# PS-001.net
KiCad netlist of a schematic drawn in EAGLE
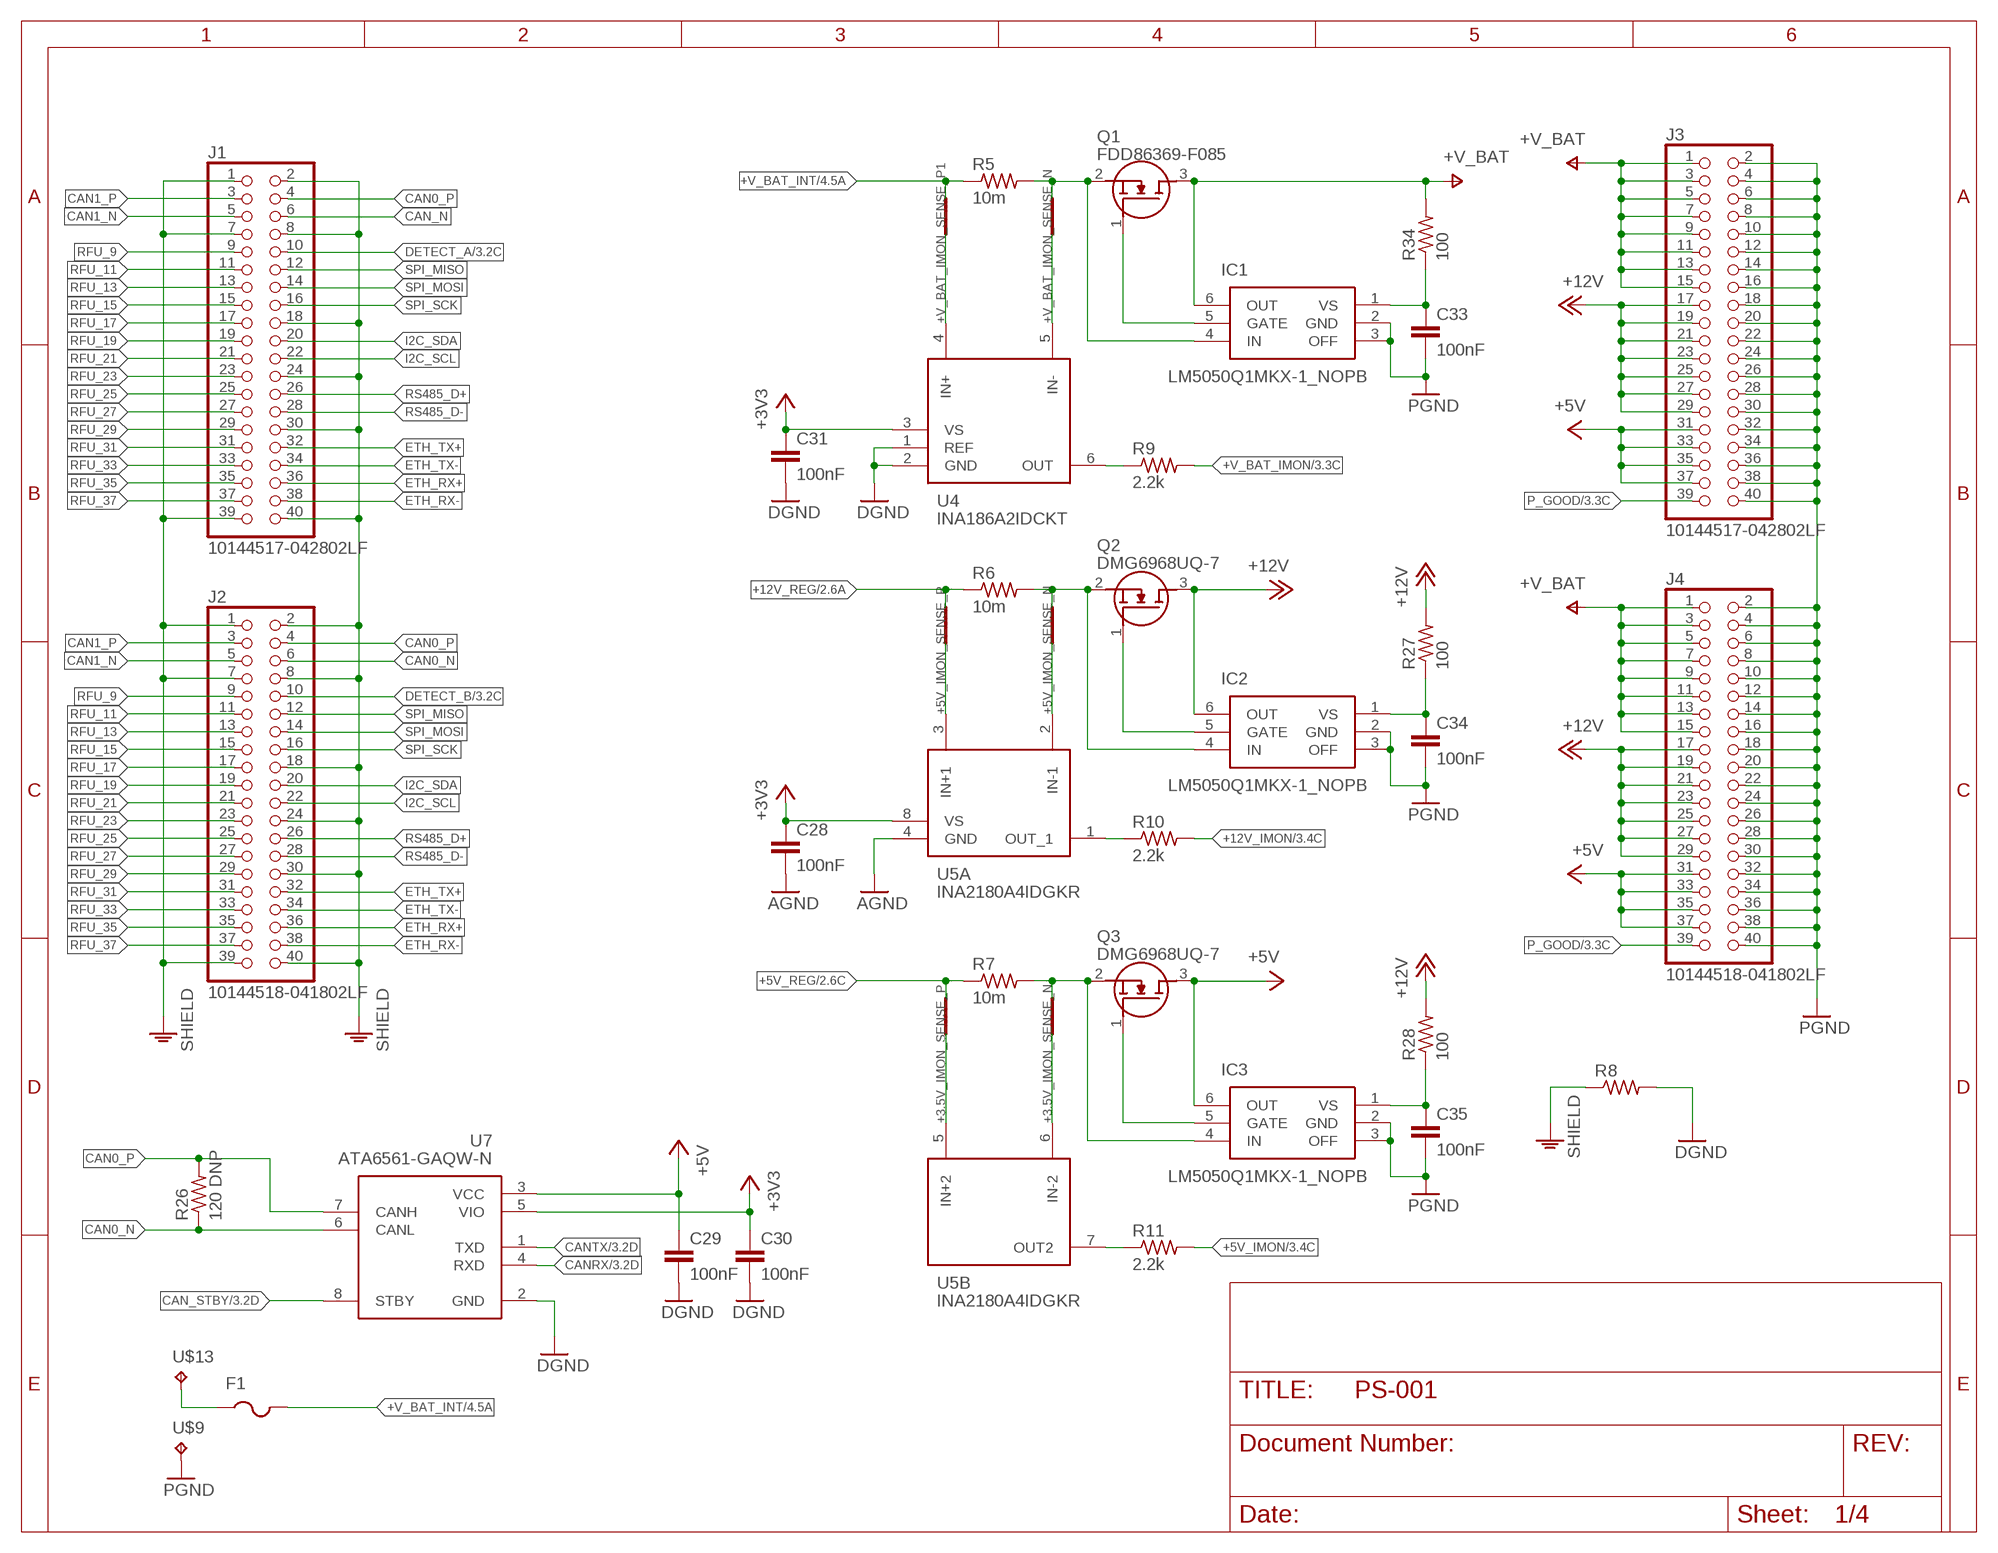
[diagram p0: schematic, sheet 1]
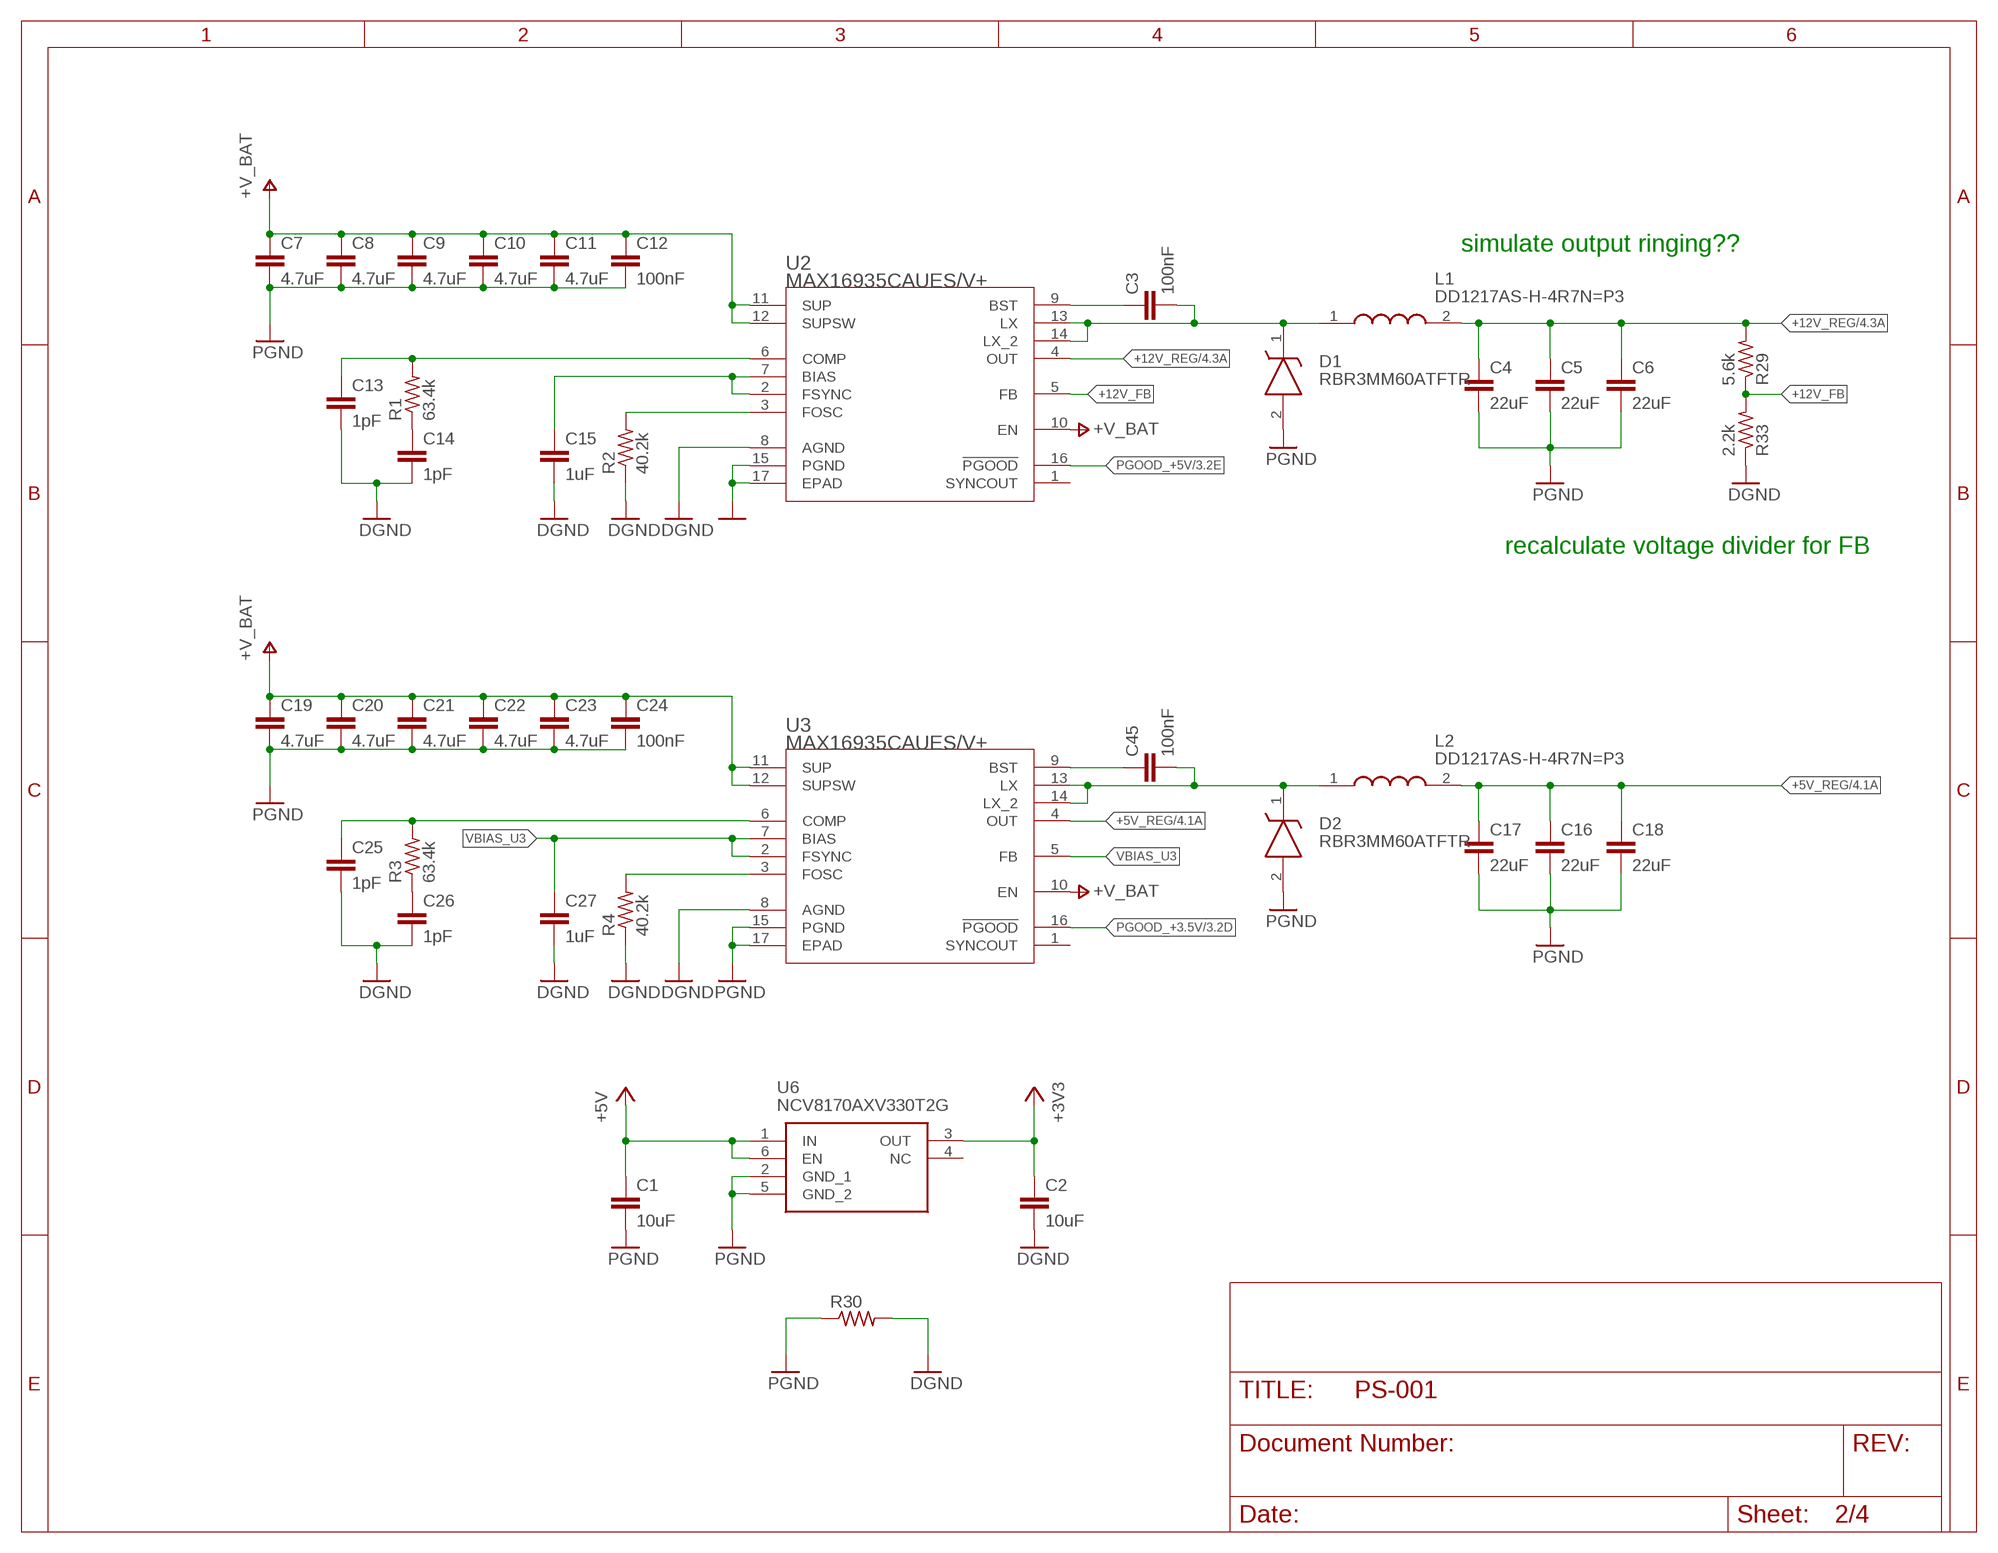
[diagram p1: schematic, sheet 2]
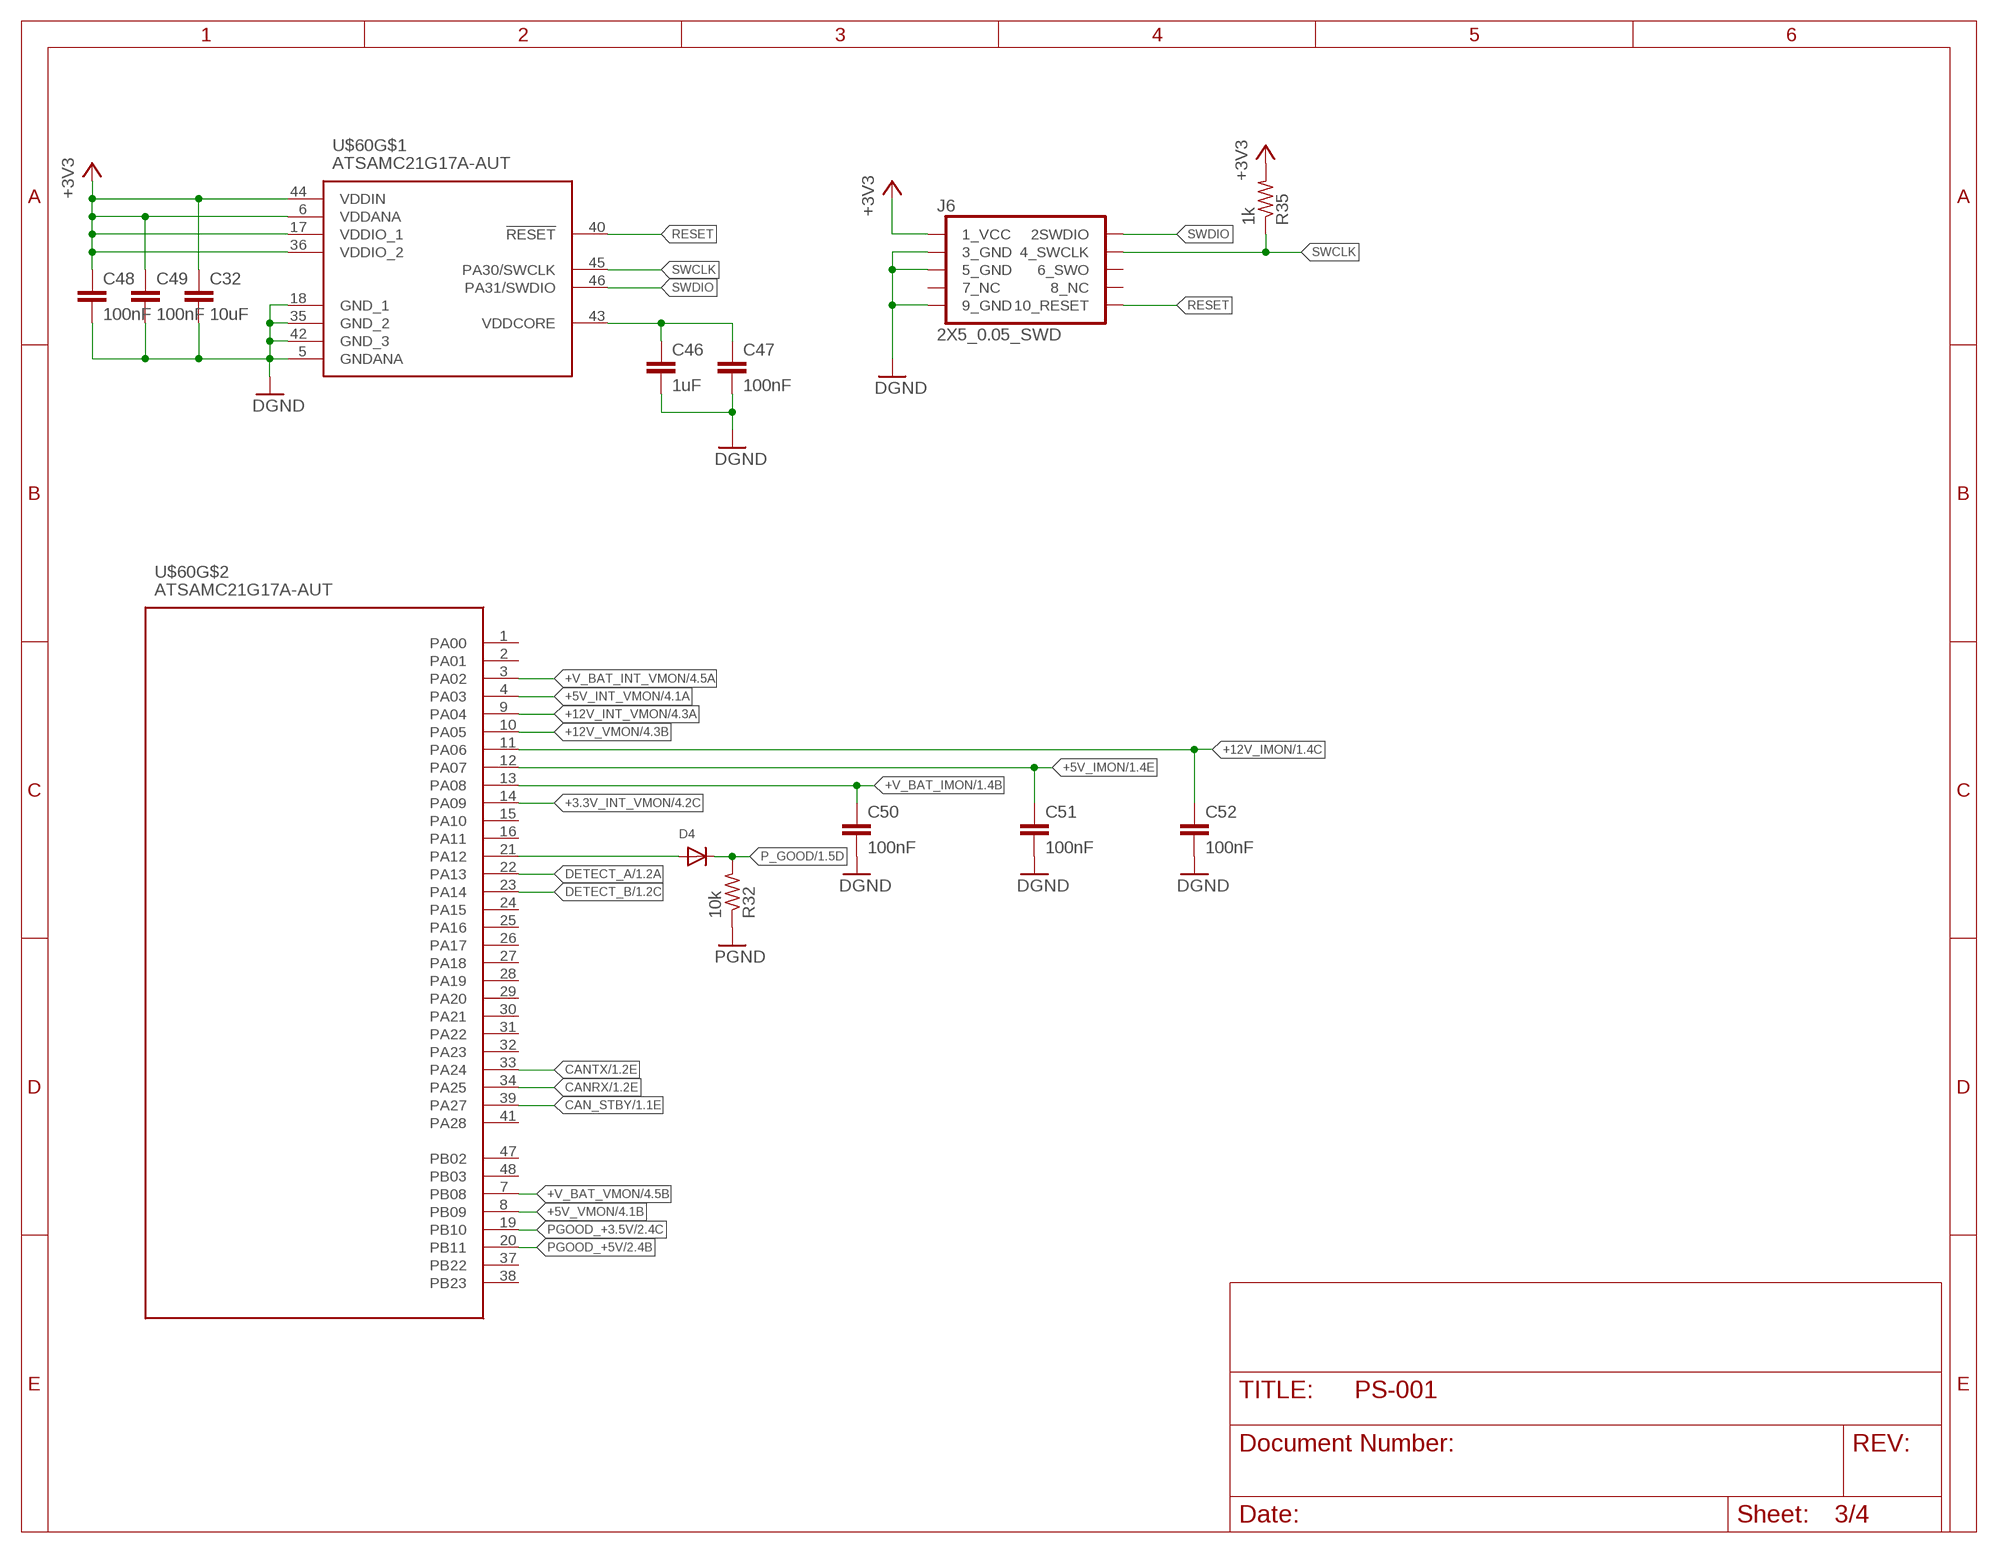
[diagram p2: schematic, sheet 3]
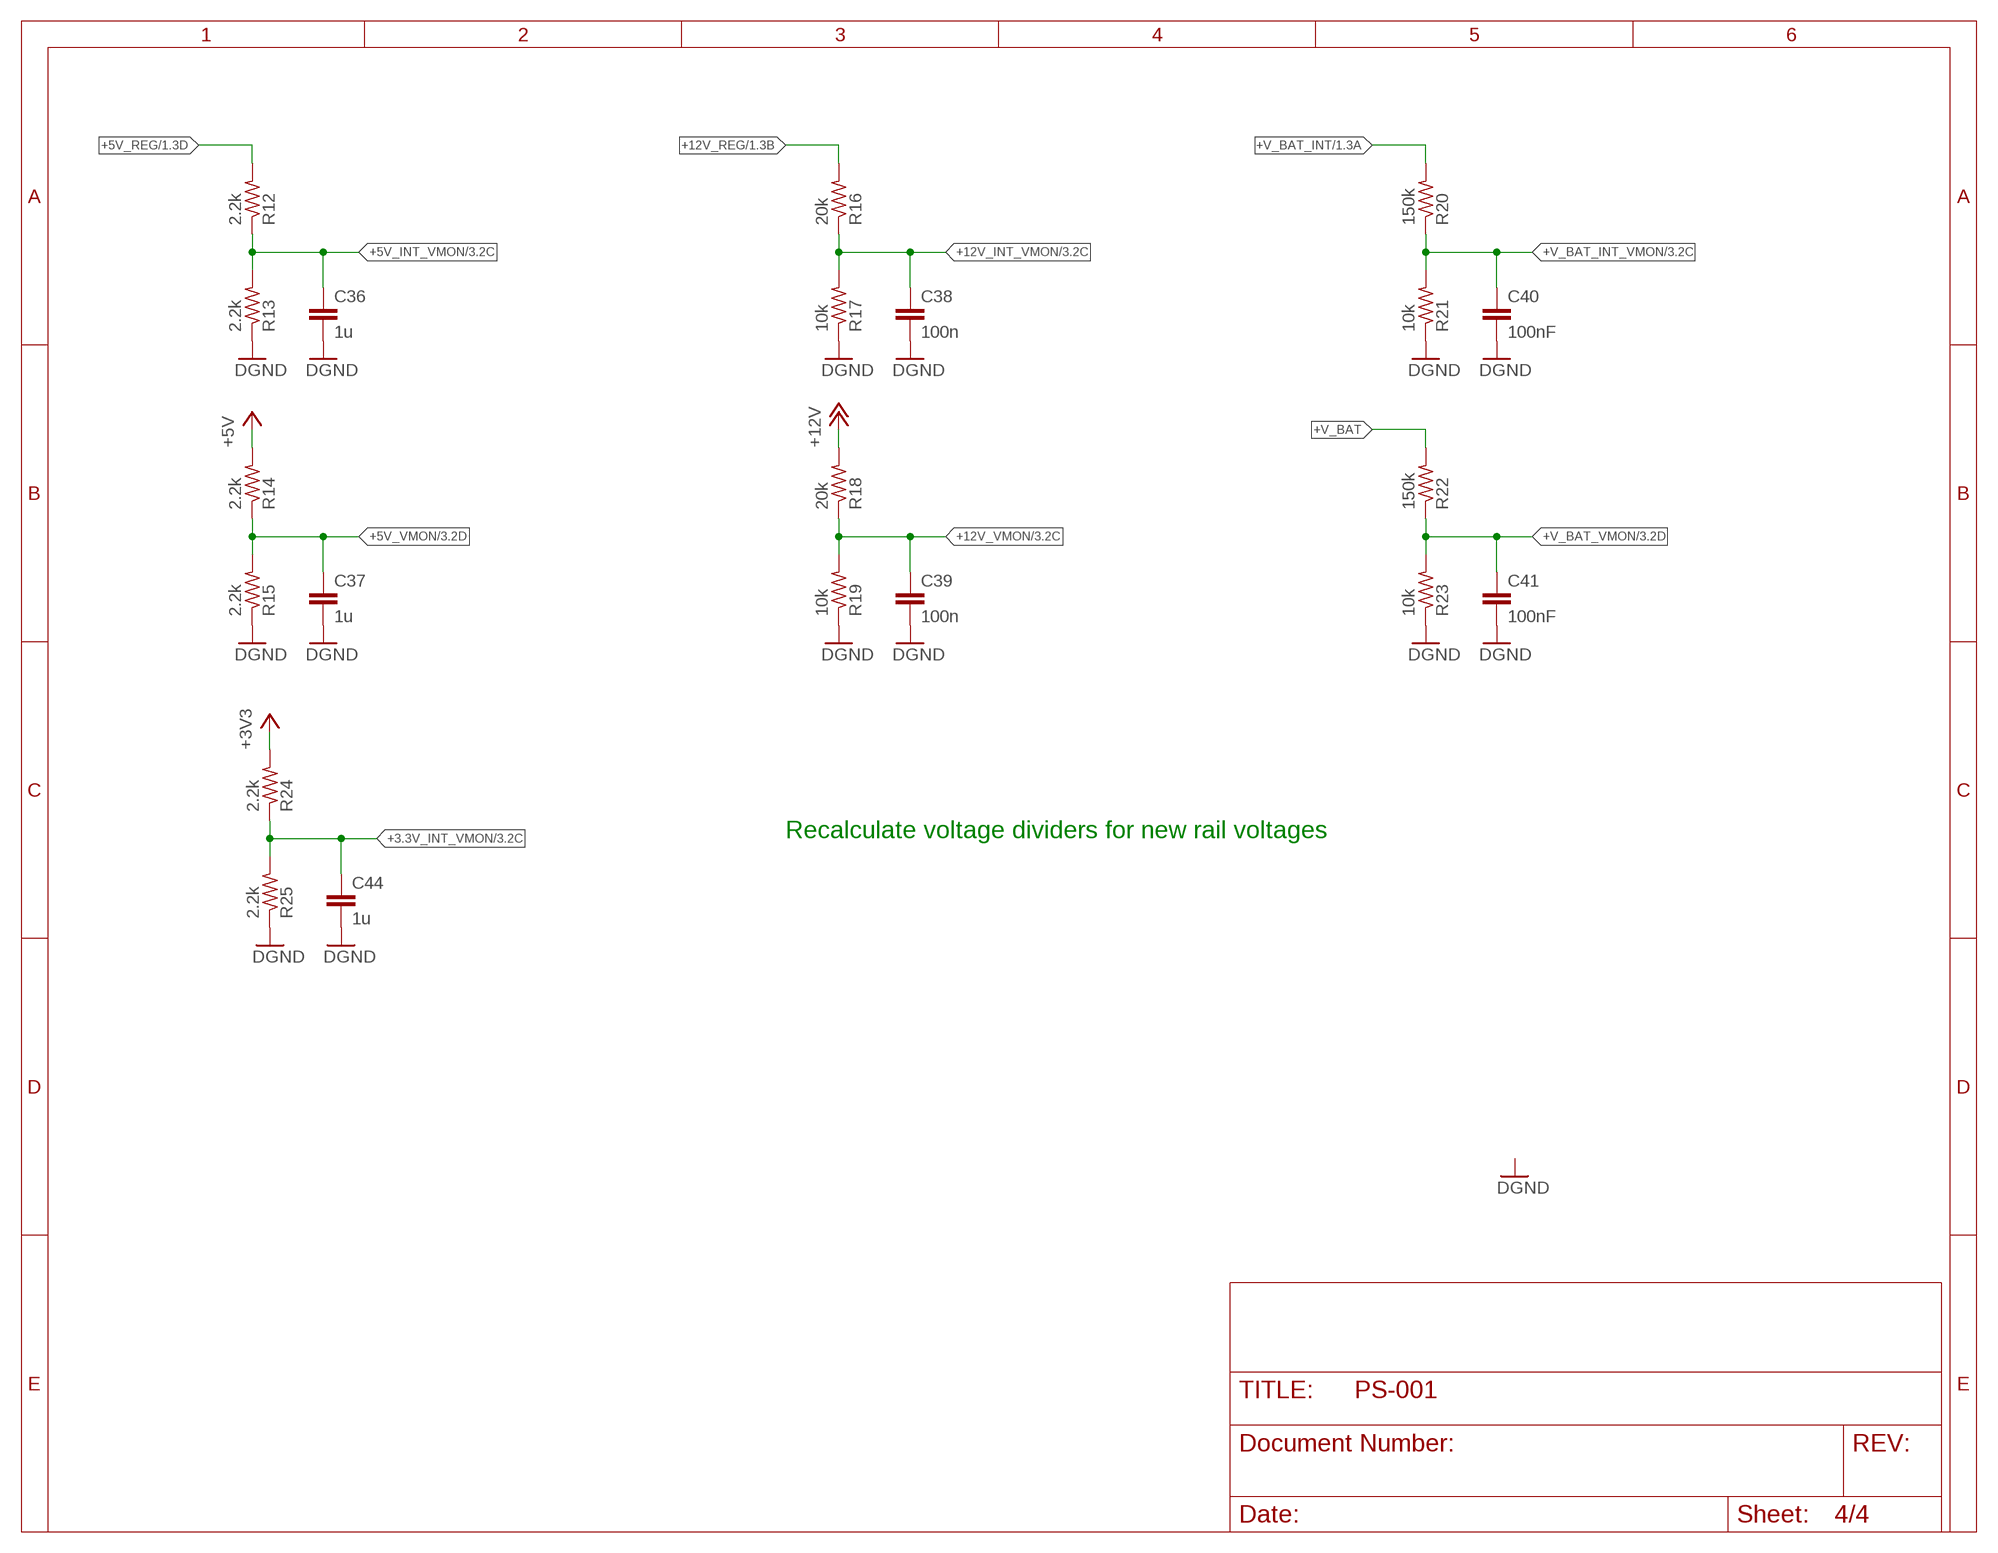
[diagram p3: schematic, sheet 4]

(export (version "E")
  (design (tool "Eeschema 10.0.6"))
  (components
    (comp (ref "C36")
      (value "1u")
      (footprint "eagle-import:C0402")
      (libsource (lib "eagle-import") (part "C-EUC0402"))
    )
    (comp (ref "C37")
      (value "1u")
      (footprint "eagle-import:C0402")
      (libsource (lib "eagle-import") (part "C-EUC0402"))
    )
    (comp (ref "C38")
      (value "100n")
      (footprint "eagle-import:C0402")
      (libsource (lib "eagle-import") (part "C-EUC0402"))
    )
    (comp (ref "C39")
      (value "100n")
      (footprint "eagle-import:C0402")
      (libsource (lib "eagle-import") (part "C-EUC0402"))
    )
    (comp (ref "C40")
      (value "100nF")
      (footprint "eagle-import:C0402")
      (libsource (lib "eagle-import") (part "C-EUC0402"))
    )
    (comp (ref "C41")
      (value "100nF")
      (footprint "eagle-import:C0402")
      (libsource (lib "eagle-import") (part "C-EUC0402"))
    )
    (comp (ref "C44")
      (value "1u")
      (footprint "eagle-import:C0402")
      (libsource (lib "eagle-import") (part "C-EUC0402"))
    )
    (comp (ref "R12")
      (value "2.2k")
      (footprint "eagle-import:R0402")
      (libsource (lib "eagle-import") (part "R-US_R0402"))
    )
    (comp (ref "R13")
      (value "2.2k")
      (footprint "eagle-import:R0402")
      (libsource (lib "eagle-import") (part "R-US_R0402"))
    )
    (comp (ref "R14")
      (value "2.2k")
      (footprint "eagle-import:R0402")
      (libsource (lib "eagle-import") (part "R-US_R0402"))
    )
    (comp (ref "R15")
      (value "2.2k")
      (footprint "eagle-import:R0402")
      (libsource (lib "eagle-import") (part "R-US_R0402"))
    )
    (comp (ref "R16")
      (value "20k")
      (footprint "eagle-import:R0402")
      (libsource (lib "eagle-import") (part "R-US_R0402"))
    )
    (comp (ref "R17")
      (value "10k")
      (footprint "eagle-import:R0402")
      (libsource (lib "eagle-import") (part "R-US_R0402"))
    )
    (comp (ref "R18")
      (value "20k")
      (footprint "eagle-import:R0402")
      (libsource (lib "eagle-import") (part "R-US_R0402"))
    )
    (comp (ref "R19")
      (value "10k")
      (footprint "eagle-import:R0402")
      (libsource (lib "eagle-import") (part "R-US_R0402"))
    )
    (comp (ref "R20")
      (value "150k")
      (footprint "eagle-import:R0402")
      (libsource (lib "eagle-import") (part "R-US_R0402"))
    )
    (comp (ref "R21")
      (value "10k")
      (footprint "eagle-import:R0402")
      (libsource (lib "eagle-import") (part "R-US_R0402"))
    )
    (comp (ref "R22")
      (value "150k")
      (footprint "eagle-import:R0402")
      (libsource (lib "eagle-import") (part "R-US_R0402"))
    )
    (comp (ref "R23")
      (value "10k")
      (footprint "eagle-import:R0402")
      (libsource (lib "eagle-import") (part "R-US_R0402"))
    )
    (comp (ref "R24")
      (value "2.2k")
      (footprint "eagle-import:R0402")
      (libsource (lib "eagle-import") (part "R-US_R0402"))
    )
    (comp (ref "R25")
      (value "2.2k")
      (footprint "eagle-import:R0402")
      (libsource (lib "eagle-import") (part "R-US_R0402"))
    )
    (comp (ref "C32")
      (value "10uF")
      (footprint "eagle-import:C0805")
      (libsource (lib "eagle-import") (part "C-EUC0805"))
    )
    (comp (ref "C46")
      (value "1uF")
      (footprint "eagle-import:C0805")
      (libsource (lib "eagle-import") (part "C-EUC0805"))
    )
    (comp (ref "C47")
      (value "100nF")
      (footprint "eagle-import:C0805")
      (libsource (lib "eagle-import") (part "C-EUC0805"))
    )
    (comp (ref "C48")
      (value "100nF")
      (footprint "eagle-import:C0402")
      (libsource (lib "eagle-import") (part "C-EUC0402"))
    )
    (comp (ref "C49")
      (value "100nF")
      (footprint "eagle-import:C0402")
      (libsource (lib "eagle-import") (part "C-EUC0402"))
    )
    (comp (ref "C50")
      (value "100nF")
      (footprint "eagle-import:C0402")
      (libsource (lib "eagle-import") (part "C-EUC0402"))
    )
    (comp (ref "C51")
      (value "100nF")
      (footprint "eagle-import:C0402")
      (libsource (lib "eagle-import") (part "C-EUC0402"))
    )
    (comp (ref "C52")
      (value "100nF")
      (footprint "eagle-import:C0402")
      (libsource (lib "eagle-import") (part "C-EUC0402"))
    )
    (comp (ref "D4")
      (value "DIODESOD-123")
      (footprint "eagle-import:SOD-123")
      (libsource (lib "eagle-import") (part "DIODESOD-123"))
    )
    (comp (ref "J6")
      (value "2X5_0.05_SWD")
      (footprint "eagle-import:2X5_RIGHT")
      (libsource (lib "eagle-import") (part "2X5_0.05_SWD"))
    )
    (comp (ref "R32")
      (value "10k")
      (footprint "eagle-import:R0402")
      (libsource (lib "eagle-import") (part "R-US_R0402"))
    )
    (comp (ref "R35")
      (value "1k")
      (footprint "eagle-import:R0402")
      (libsource (lib "eagle-import") (part "R-US_R0402"))
    )
    (comp (ref "U$60")
      (value "ATSAMC21G17A-AUT")
      (footprint "eagle-import:QFP50P900X900X120-48N")
      (libsource (lib "eagle-import") (part "ATSAMC21G17A-AUT"))
    )
    (comp (ref "C1")
      (value "10uF")
      (footprint "eagle-import:C0805")
      (libsource (lib "eagle-import") (part "C-EUC0805"))
    )
    (comp (ref "C2")
      (value "10uF")
      (footprint "eagle-import:C0805")
      (libsource (lib "eagle-import") (part "C-EUC0805"))
    )
    (comp (ref "C3")
      (value "100nF")
      (footprint "eagle-import:C0603")
      (libsource (lib "eagle-import") (part "C-EUC0603"))
    )
    (comp (ref "C4")
      (value "22uF")
      (footprint "eagle-import:C1206")
      (libsource (lib "eagle-import") (part "C-EUC1206"))
    )
    (comp (ref "C5")
      (value "22uF")
      (footprint "eagle-import:C1206")
      (libsource (lib "eagle-import") (part "C-EUC1206"))
    )
    (comp (ref "C6")
      (value "22uF")
      (footprint "eagle-import:C1206")
      (libsource (lib "eagle-import") (part "C-EUC1206"))
    )
    (comp (ref "C7")
      (value "4.7uF")
      (footprint "eagle-import:C0805")
      (libsource (lib "eagle-import") (part "C-EUC0805"))
    )
    (comp (ref "C8")
      (value "4.7uF")
      (footprint "eagle-import:C0805")
      (libsource (lib "eagle-import") (part "C-EUC0805"))
    )
    (comp (ref "C9")
      (value "4.7uF")
      (footprint "eagle-import:C0805")
      (libsource (lib "eagle-import") (part "C-EUC0805"))
    )
    (comp (ref "C10")
      (value "4.7uF")
      (footprint "eagle-import:C0805")
      (libsource (lib "eagle-import") (part "C-EUC0805"))
    )
    (comp (ref "C11")
      (value "4.7uF")
      (footprint "eagle-import:C0805")
      (libsource (lib "eagle-import") (part "C-EUC0805"))
    )
    (comp (ref "C12")
      (value "100nF")
      (footprint "eagle-import:C0603")
      (libsource (lib "eagle-import") (part "C-EUC0603"))
    )
    (comp (ref "C13")
      (value "1pF")
      (footprint "eagle-import:C0402")
      (libsource (lib "eagle-import") (part "C-EUC0402"))
    )
    (comp (ref "C14")
      (value "1pF")
      (footprint "eagle-import:C0402")
      (libsource (lib "eagle-import") (part "C-EUC0402"))
    )
    (comp (ref "C15")
      (value "1uF")
      (footprint "eagle-import:C0402")
      (libsource (lib "eagle-import") (part "C-EUC0402"))
    )
    (comp (ref "C16")
      (value "22uF")
      (footprint "eagle-import:C1206")
      (libsource (lib "eagle-import") (part "C-EUC1206"))
    )
    (comp (ref "C17")
      (value "22uF")
      (footprint "eagle-import:C1206")
      (libsource (lib "eagle-import") (part "C-EUC1206"))
    )
    (comp (ref "C18")
      (value "22uF")
      (footprint "eagle-import:C1206")
      (libsource (lib "eagle-import") (part "C-EUC1206"))
    )
    (comp (ref "C19")
      (value "4.7uF")
      (footprint "eagle-import:C0805")
      (libsource (lib "eagle-import") (part "C-EUC0805"))
    )
    (comp (ref "C20")
      (value "4.7uF")
      (footprint "eagle-import:C0805")
      (libsource (lib "eagle-import") (part "C-EUC0805"))
    )
    (comp (ref "C21")
      (value "4.7uF")
      (footprint "eagle-import:C0805")
      (libsource (lib "eagle-import") (part "C-EUC0805"))
    )
    (comp (ref "C22")
      (value "4.7uF")
      (footprint "eagle-import:C0805")
      (libsource (lib "eagle-import") (part "C-EUC0805"))
    )
    (comp (ref "C23")
      (value "4.7uF")
      (footprint "eagle-import:C0805")
      (libsource (lib "eagle-import") (part "C-EUC0805"))
    )
    (comp (ref "C24")
      (value "100nF")
      (footprint "eagle-import:C0603")
      (libsource (lib "eagle-import") (part "C-EUC0603"))
    )
    (comp (ref "C25")
      (value "1pF")
      (footprint "eagle-import:C0402")
      (libsource (lib "eagle-import") (part "C-EUC0402"))
    )
    (comp (ref "C26")
      (value "1pF")
      (footprint "eagle-import:C0402")
      (libsource (lib "eagle-import") (part "C-EUC0402"))
    )
    (comp (ref "C27")
      (value "1uF")
      (footprint "eagle-import:C0402")
      (libsource (lib "eagle-import") (part "C-EUC0402"))
    )
    (comp (ref "C45")
      (value "100nF")
      (footprint "eagle-import:C0603")
      (libsource (lib "eagle-import") (part "C-EUC0603"))
    )
    (comp (ref "D1")
      (value "RBR3MM60ATFTR")
      (footprint "eagle-import:PMDU")
      (fields (field (name "MOUSER_PART_NUMBER") "755-RBR3MM60ATFTR"))
      (libsource (lib "eagle-import") (part "RBR3MM60ATFTR"))
    )
    (comp (ref "D2")
      (value "RBR3MM60ATFTR")
      (footprint "eagle-import:PMDU")
      (fields (field (name "MOUSER_PART_NUMBER") "755-RBR3MM60ATFTR"))
      (libsource (lib "eagle-import") (part "RBR3MM60ATFTR"))
    )
    (comp (ref "L1")
      (value "DD1217AS-H-4R7N=P3")
      (footprint "eagle-import:INDPM8282X450N")
      (libsource (lib "eagle-import") (part "DD1217AS-H-4R7N=P3"))
    )
    (comp (ref "L2")
      (value "DD1217AS-H-4R7N=P3")
      (footprint "eagle-import:INDPM8282X450N")
      (libsource (lib "eagle-import") (part "DD1217AS-H-4R7N=P3"))
    )
    (comp (ref "R1")
      (value "63.4k")
      (footprint "eagle-import:R0603")
      (libsource (lib "eagle-import") (part "R-US_R0603"))
    )
    (comp (ref "R2")
      (value "40.2k")
      (footprint "eagle-import:R0603")
      (libsource (lib "eagle-import") (part "R-US_R0603"))
    )
    (comp (ref "R3")
      (value "63.4k")
      (footprint "eagle-import:R0603")
      (libsource (lib "eagle-import") (part "R-US_R0603"))
    )
    (comp (ref "R4")
      (value "40.2k")
      (footprint "eagle-import:R0603")
      (libsource (lib "eagle-import") (part "R-US_R0603"))
    )
    (comp (ref "R29")
      (value "5.6k")
      (footprint "eagle-import:R0402")
      (libsource (lib "eagle-import") (part "R-US_R0402"))
    )
    (comp (ref "R30")
      (value "R-US_R0402")
      (footprint "eagle-import:R0402")
      (libsource (lib "eagle-import") (part "R-US_R0402"))
    )
    (comp (ref "R33")
      (value "2.2k")
      (footprint "eagle-import:R0402")
      (libsource (lib "eagle-import") (part "R-US_R0402"))
    )
    (comp (ref "U2")
      (value "MAX16935CAUES/V+")
      (footprint "eagle-import:21-0108G_U16E-3")
      (fields (field (name "MANUFACTURER_PART_NUMBER") "MAX16935CAUESV+"))
      (libsource (lib "eagle-import") (part "MAX16935CAUES/V+"))
    )
    (comp (ref "U3")
      (value "MAX16935CAUES/V+")
      (footprint "eagle-import:21-0108G_U16E-3")
      (fields (field (name "MANUFACTURER_PART_NUMBER") "MAX16935CAUESV+"))
      (libsource (lib "eagle-import") (part "MAX16935CAUES/V+"))
    )
    (comp (ref "U6")
      (value "NCV8170AXV330T2G")
      (footprint "eagle-import:SOTFL50P160X60-6N")
      (fields (field (name "MOUSER_PART_NUMBER") "863-NCV8170AXV330T2G"))
      (libsource (lib "eagle-import") (part "NCV8170AXV330T2G"))
    )
    (comp (ref "C28")
      (value "100nF")
      (footprint "eagle-import:C0402")
      (libsource (lib "eagle-import") (part "C-EUC0402"))
    )
    (comp (ref "C29")
      (value "100nF")
      (footprint "eagle-import:C0402")
      (libsource (lib "eagle-import") (part "C-EUC0402"))
    )
    (comp (ref "C30")
      (value "100nF")
      (footprint "eagle-import:C0402")
      (libsource (lib "eagle-import") (part "C-EUC0402"))
    )
    (comp (ref "C31")
      (value "100nF")
      (footprint "eagle-import:C0402")
      (libsource (lib "eagle-import") (part "C-EUC0402"))
    )
    (comp (ref "C33")
      (value "100nF")
      (footprint "eagle-import:C0402")
      (libsource (lib "eagle-import") (part "C-EUC0402"))
    )
    (comp (ref "C34")
      (value "100nF")
      (footprint "eagle-import:C0402")
      (libsource (lib "eagle-import") (part "C-EUC0402"))
    )
    (comp (ref "C35")
      (value "100nF")
      (footprint "eagle-import:C0402")
      (libsource (lib "eagle-import") (part "C-EUC0402"))
    )
    (comp (ref "F1")
      (value "PTCFUSE-1206")
      (footprint "eagle-import:R1206")
      (libsource (lib "eagle-import") (part "PTCFUSE-1206"))
    )
    (comp (ref "IC1")
      (value "LM5050Q1MKX-1_NOPB")
      (footprint "eagle-import:SOT95P280X110-6N")
      (fields
        (field (name "MANUFACTURER_PART_NUMBER") "LM5050Q1MKX-1/NOPB")
        (field (name "MOUSER_PART_NUMBER") "595-LM5050Q1MKX1NOPB")
      )
      (libsource (lib "eagle-import") (part "LM5050Q1MKX-1_NOPB"))
    )
    (comp (ref "IC2")
      (value "LM5050Q1MKX-1_NOPB")
      (footprint "eagle-import:SOT95P280X110-6N")
      (fields
        (field (name "MANUFACTURER_PART_NUMBER") "LM5050Q1MKX-1/NOPB")
        (field (name "MOUSER_PART_NUMBER") "595-LM5050Q1MKX1NOPB")
      )
      (libsource (lib "eagle-import") (part "LM5050Q1MKX-1_NOPB"))
    )
    (comp (ref "IC3")
      (value "LM5050Q1MKX-1_NOPB")
      (footprint "eagle-import:SOT95P280X110-6N")
      (fields
        (field (name "MANUFACTURER_PART_NUMBER") "LM5050Q1MKX-1/NOPB")
        (field (name "MOUSER_PART_NUMBER") "595-LM5050Q1MKX1NOPB")
      )
      (libsource (lib "eagle-import") (part "LM5050Q1MKX-1_NOPB"))
    )
    (comp (ref "J1")
      (value "10144517-042802LF")
      (footprint "eagle-import:10144517-042802LF")
      (libsource (lib "eagle-import") (part "10144517-042802LF"))
    )
    (comp (ref "J2")
      (value "10144518-041802LF")
      (footprint "eagle-import:10144518-041802LF")
      (libsource (lib "eagle-import") (part "10144518-041802LF"))
    )
    (comp (ref "J3")
      (value "10144517-042802LF")
      (footprint "eagle-import:10144517-042802LF")
      (libsource (lib "eagle-import") (part "10144517-042802LF"))
    )
    (comp (ref "J4")
      (value "10144518-041802LF")
      (footprint "eagle-import:10144518-041802LF")
      (libsource (lib "eagle-import") (part "10144518-041802LF"))
    )
    (comp (ref "Q1")
      (value "FDD86369-F085")
      (footprint "eagle-import:DPAK3-CASE-369AS")
      (fields (field (name "MOUSER_PART_NUMBER") "512-FDD86369_F085"))
      (libsource (lib "eagle-import") (part "FDD86369-F085"))
    )
    (comp (ref "Q2")
      (value "DMG6968UQ-7")
      (footprint "eagle-import:SOT96P240X100-3N")
      (fields (field (name "MOUSER_PART_NUMBER") "621-DMG6968UQ-7"))
      (libsource (lib "eagle-import") (part "DMG6968UQ-7"))
    )
    (comp (ref "Q3")
      (value "DMG6968UQ-7")
      (footprint "eagle-import:SOT96P240X100-3N")
      (fields (field (name "MOUSER_PART_NUMBER") "621-DMG6968UQ-7"))
      (libsource (lib "eagle-import") (part "DMG6968UQ-7"))
    )
    (comp (ref "R5")
      (value "10m")
      (footprint "eagle-import:R0603")
      (libsource (lib "eagle-import") (part "R-US_R0603"))
    )
    (comp (ref "R6")
      (value "10m")
      (footprint "eagle-import:R0603")
      (libsource (lib "eagle-import") (part "R-US_R0603"))
    )
    (comp (ref "R7")
      (value "10m")
      (footprint "eagle-import:R0603")
      (libsource (lib "eagle-import") (part "R-US_R0603"))
    )
    (comp (ref "R8")
      (value "R-US_R0402")
      (footprint "eagle-import:R0402")
      (libsource (lib "eagle-import") (part "R-US_R0402"))
    )
    (comp (ref "R9")
      (value "2.2k")
      (footprint "eagle-import:R0402")
      (libsource (lib "eagle-import") (part "R-US_R0402"))
    )
    (comp (ref "R10")
      (value "2.2k")
      (footprint "eagle-import:R0402")
      (libsource (lib "eagle-import") (part "R-US_R0402"))
    )
    (comp (ref "R11")
      (value "2.2k")
      (footprint "eagle-import:R0402")
      (libsource (lib "eagle-import") (part "R-US_R0402"))
    )
    (comp (ref "R26")
      (value "120 DNP")
      (footprint "eagle-import:R0402")
      (libsource (lib "eagle-import") (part "R-US_R0402"))
    )
    (comp (ref "R27")
      (value "100")
      (footprint "eagle-import:R0402")
      (libsource (lib "eagle-import") (part "R-US_R0402"))
    )
    (comp (ref "R28")
      (value "100")
      (footprint "eagle-import:R0402")
      (libsource (lib "eagle-import") (part "R-US_R0402"))
    )
    (comp (ref "R34")
      (value "100")
      (footprint "eagle-import:R0402")
      (libsource (lib "eagle-import") (part "R-US_R0402"))
    )
    (comp (ref "SH1")
      (value "SHORTT8")
      (footprint "eagle-import:SHORT_TOP-8")
      (libsource (lib "eagle-import") (part "SHORTT8"))
    )
    (comp (ref "SH2")
      (value "SHORTT8")
      (footprint "eagle-import:SHORT_TOP-8")
      (libsource (lib "eagle-import") (part "SHORTT8"))
    )
    (comp (ref "SH3")
      (value "SHORTT8")
      (footprint "eagle-import:SHORT_TOP-8")
      (libsource (lib "eagle-import") (part "SHORTT8"))
    )
    (comp (ref "SH4")
      (value "SHORTT8")
      (footprint "eagle-import:SHORT_TOP-8")
      (libsource (lib "eagle-import") (part "SHORTT8"))
    )
    (comp (ref "SH5")
      (value "SHORTT8")
      (footprint "eagle-import:SHORT_TOP-8")
      (libsource (lib "eagle-import") (part "SHORTT8"))
    )
    (comp (ref "SH6")
      (value "SHORTT8")
      (footprint "eagle-import:SHORT_TOP-8")
      (libsource (lib "eagle-import") (part "SHORTT8"))
    )
    (comp (ref "U$9")
      (value "WIRE-PAD")
      (footprint "eagle-import:12AWG-STRANDED")
      (libsource (lib "eagle-import") (part "WIRE-PAD"))
    )
    (comp (ref "U$13")
      (value "WIRE-PAD")
      (footprint "eagle-import:12AWG-STRANDED")
      (libsource (lib "eagle-import") (part "WIRE-PAD"))
    )
    (comp (ref "U4")
      (value "INA186A2IDCKT")
      (footprint "eagle-import:SOT65P210X110-6N")
      (fields (field (name "MOUSER_PART_NUMBER") "595-INA186A2IDCKT"))
      (libsource (lib "eagle-import") (part "INA186A2IDCKT"))
    )
    (comp (ref "U5")
      (value "INA2180A4IDGKR")
      (footprint "eagle-import:SOP65P490X110-8N")
      (fields
        (field (name "MANUFACTURER_PART_NUMBER") "INA2180A2IDGKR")
        (field (name "MOUSER_PART_NUMBER") "595-INA2180A2IDGKR")
      )
      (libsource (lib "eagle-import") (part "INA2180A2IDGKR"))
    )
    (comp (ref "U7")
      (value "ATA6561-GAQW-N")
      (footprint "eagle-import:SOIC127P600X175-8N")
      (fields (field (name "MOUSER_PART_NUMBER") "579-ATA6561-GAQW-N"))
      (libsource (lib "eagle-import") (part "ATA6561-GAQW-N"))
    )
  )
  (nets
    (net (code "1") (name "+3.3V_INT_VMON") (class "Default")
      (node (ref "C44") (pin "1") (pinfunction "1_1") (pintype "passive"))
      (node (ref "R24") (pin "1") (pinfunction "1_1") (pintype "passive"))
      (node (ref "R25") (pin "2") (pinfunction "2_2") (pintype "passive"))
      (node (ref "U$60") (pin "14") (pinfunction "PA09_14") (pintype "bidirectional"))
    )
    (net (code "2") (name "+3.5V_IMON_SENSE_N") (class "Default")
      (node (ref "SH2") (pin "1") (pinfunction "P$1_1") (pintype "bidirectional"))
      (node (ref "U5") (pin "6") (pinfunction "IN-2_6") (pintype "bidirectional"))
    )
    (net (code "3") (name "+3.5V_IMON_SENSE_P") (class "Default")
      (node (ref "SH1") (pin "1") (pinfunction "P$1_1") (pintype "bidirectional"))
      (node (ref "U5") (pin "5") (pinfunction "IN+2_5") (pintype "bidirectional"))
    )
    (net (code "4") (name "+3V3") (class "Default")
      (node (ref "C2") (pin "1") (pinfunction "1_1") (pintype "passive"))
      (node (ref "C28") (pin "1") (pinfunction "1_1") (pintype "passive"))
      (node (ref "C30") (pin "1") (pinfunction "1_1") (pintype "passive"))
      (node (ref "C31") (pin "1") (pinfunction "1_1") (pintype "passive"))
      (node (ref "C32") (pin "1") (pinfunction "1_1") (pintype "passive"))
      (node (ref "C48") (pin "1") (pinfunction "1_1") (pintype "passive"))
      (node (ref "C49") (pin "1") (pinfunction "1_1") (pintype "passive"))
      (node (ref "J6") (pin "1") (pinfunction "1_VCC_1") (pintype "passive"))
      (node (ref "R24") (pin "2") (pinfunction "2_2") (pintype "passive"))
      (node (ref "R35") (pin "2") (pinfunction "2_2") (pintype "passive"))
      (node (ref "U$60") (pin "17") (pinfunction "VDDIO_1_17") (pintype "bidirectional"))
      (node (ref "U$60") (pin "36") (pinfunction "VDDIO_2_36") (pintype "bidirectional"))
      (node (ref "U$60") (pin "44") (pinfunction "VDDIN_44") (pintype "power_in"))
      (node (ref "U$60") (pin "6") (pinfunction "VDDANA_6") (pintype "power_in"))
      (node (ref "U4") (pin "3") (pinfunction "VS_3") (pintype "bidirectional"))
      (node (ref "U5") (pin "8") (pinfunction "VS_8") (pintype "bidirectional"))
      (node (ref "U6") (pin "3") (pinfunction "OUT_3") (pintype "bidirectional"))
      (node (ref "U7") (pin "5") (pinfunction "VIO_5") (pintype "bidirectional"))
    )
    (net (code "5") (name "+5V") (class "Default")
      (node (ref "C1") (pin "1") (pinfunction "1_1") (pintype "passive"))
      (node (ref "C29") (pin "1") (pinfunction "1_1") (pintype "passive"))
      (node (ref "IC3") (pin "6") (pinfunction "OUT_6") (pintype "bidirectional"))
      (node (ref "J3") (pin "31") (pinfunction "31_31") (pintype "passive"))
      (node (ref "J3") (pin "33") (pinfunction "33_33") (pintype "passive"))
      (node (ref "J3") (pin "35") (pinfunction "35_35") (pintype "passive"))
      (node (ref "J3") (pin "37") (pinfunction "37_37") (pintype "passive"))
      (node (ref "J4") (pin "31") (pinfunction "31_31") (pintype "passive"))
      (node (ref "J4") (pin "33") (pinfunction "33_33") (pintype "passive"))
      (node (ref "J4") (pin "35") (pinfunction "35_35") (pintype "passive"))
      (node (ref "J4") (pin "37") (pinfunction "37_37") (pintype "passive"))
      (node (ref "Q3") (pin "3") (pinfunction "D_3") (pintype "bidirectional"))
      (node (ref "R14") (pin "2") (pinfunction "2_2") (pintype "passive"))
      (node (ref "U6") (pin "1") (pinfunction "IN_1") (pintype "bidirectional"))
      (node (ref "U6") (pin "6") (pinfunction "EN_6") (pintype "bidirectional"))
      (node (ref "U7") (pin "3") (pinfunction "VCC_3") (pintype "bidirectional"))
    )
    (net (code "6") (name "+5V_IMON") (class "Default")
      (node (ref "C51") (pin "1") (pinfunction "1_1") (pintype "passive"))
      (node (ref "R11") (pin "2") (pinfunction "2_2") (pintype "passive"))
      (node (ref "U$60") (pin "12") (pinfunction "PA07_12") (pintype "bidirectional"))
    )
    (net (code "7") (name "+5V_IMON_SENSE_N") (class "Default")
      (node (ref "SH4") (pin "1") (pinfunction "P$1_1") (pintype "bidirectional"))
      (node (ref "U5") (pin "2") (pinfunction "IN-1_2") (pintype "bidirectional"))
    )
    (net (code "8") (name "+5V_IMON_SENSE_P") (class "Default")
      (node (ref "SH3") (pin "1") (pinfunction "P$1_1") (pintype "bidirectional"))
      (node (ref "U5") (pin "3") (pinfunction "IN+1_3") (pintype "bidirectional"))
    )
    (net (code "9") (name "+5V_INT_VMON") (class "Default")
      (node (ref "C36") (pin "1") (pinfunction "1_1") (pintype "passive"))
      (node (ref "R12") (pin "1") (pinfunction "1_1") (pintype "passive"))
      (node (ref "R13") (pin "2") (pinfunction "2_2") (pintype "passive"))
      (node (ref "U$60") (pin "4") (pinfunction "PA03_4") (pintype "bidirectional"))
    )
    (net (code "10") (name "+5V_REG") (class "Default")
      (node (ref "C16") (pin "1") (pinfunction "1_1") (pintype "passive"))
      (node (ref "C17") (pin "1") (pinfunction "1_1") (pintype "passive"))
      (node (ref "C18") (pin "1") (pinfunction "1_1") (pintype "passive"))
      (node (ref "L2") (pin "2") (pinfunction "2_2") (pintype "bidirectional"))
      (node (ref "R12") (pin "2") (pinfunction "2_2") (pintype "passive"))
      (node (ref "R7") (pin "1") (pinfunction "1_1") (pintype "passive"))
      (node (ref "SH1") (pin "2") (pinfunction "P$2_2") (pintype "bidirectional"))
      (node (ref "U3") (pin "4") (pinfunction "OUT_4") (pintype "output"))
    )
    (net (code "11") (name "+5V_VMON") (class "Default")
      (node (ref "C37") (pin "1") (pinfunction "1_1") (pintype "passive"))
      (node (ref "R14") (pin "1") (pinfunction "1_1") (pintype "passive"))
      (node (ref "R15") (pin "2") (pinfunction "2_2") (pintype "passive"))
      (node (ref "U$60") (pin "8") (pinfunction "PB09_8") (pintype "bidirectional"))
    )
    (net (code "12") (name "+12V") (class "Default")
      (node (ref "IC2") (pin "6") (pinfunction "OUT_6") (pintype "bidirectional"))
      (node (ref "J3") (pin "17") (pinfunction "17_17") (pintype "passive"))
      (node (ref "J3") (pin "19") (pinfunction "19_19") (pintype "passive"))
      (node (ref "J3") (pin "21") (pinfunction "21_21") (pintype "passive"))
      (node (ref "J3") (pin "23") (pinfunction "23_23") (pintype "passive"))
      (node (ref "J3") (pin "25") (pinfunction "25_25") (pintype "passive"))
      (node (ref "J3") (pin "27") (pinfunction "27_27") (pintype "passive"))
      (node (ref "J3") (pin "29") (pinfunction "29_29") (pintype "passive"))
      (node (ref "J4") (pin "17") (pinfunction "17_17") (pintype "passive"))
      (node (ref "J4") (pin "19") (pinfunction "19_19") (pintype "passive"))
      (node (ref "J4") (pin "21") (pinfunction "21_21") (pintype "passive"))
      (node (ref "J4") (pin "23") (pinfunction "23_23") (pintype "passive"))
      (node (ref "J4") (pin "25") (pinfunction "25_25") (pintype "passive"))
      (node (ref "J4") (pin "27") (pinfunction "27_27") (pintype "passive"))
      (node (ref "J4") (pin "29") (pinfunction "29_29") (pintype "passive"))
      (node (ref "Q2") (pin "3") (pinfunction "D_3") (pintype "bidirectional"))
      (node (ref "R18") (pin "2") (pinfunction "2_2") (pintype "passive"))
      (node (ref "R27") (pin "2") (pinfunction "2_2") (pintype "passive"))
      (node (ref "R28") (pin "2") (pinfunction "2_2") (pintype "passive"))
    )
    (net (code "13") (name "+12V_FB") (class "Default")
      (node (ref "R29") (pin "1") (pinfunction "1_1") (pintype "passive"))
      (node (ref "R33") (pin "2") (pinfunction "2_2") (pintype "passive"))
      (node (ref "U2") (pin "5") (pinfunction "FB_5") (pintype "passive"))
    )
    (net (code "14") (name "+12V_IMON") (class "Default")
      (node (ref "C52") (pin "1") (pinfunction "1_1") (pintype "passive"))
      (node (ref "R10") (pin "2") (pinfunction "2_2") (pintype "passive"))
      (node (ref "U$60") (pin "11") (pinfunction "PA06_11") (pintype "bidirectional"))
    )
    (net (code "15") (name "+12V_INT_VMON") (class "Default")
      (node (ref "C38") (pin "1") (pinfunction "1_1") (pintype "passive"))
      (node (ref "R16") (pin "1") (pinfunction "1_1") (pintype "passive"))
      (node (ref "R17") (pin "2") (pinfunction "2_2") (pintype "passive"))
      (node (ref "U$60") (pin "9") (pinfunction "PA04_9") (pintype "bidirectional"))
    )
    (net (code "16") (name "+12V_REG") (class "Default")
      (node (ref "C4") (pin "1") (pinfunction "1_1") (pintype "passive"))
      (node (ref "C5") (pin "1") (pinfunction "1_1") (pintype "passive"))
      (node (ref "C6") (pin "1") (pinfunction "1_1") (pintype "passive"))
      (node (ref "L1") (pin "2") (pinfunction "2_2") (pintype "bidirectional"))
      (node (ref "R16") (pin "2") (pinfunction "2_2") (pintype "passive"))
      (node (ref "R29") (pin "2") (pinfunction "2_2") (pintype "passive"))
      (node (ref "R6") (pin "1") (pinfunction "1_1") (pintype "passive"))
      (node (ref "SH3") (pin "2") (pinfunction "P$2_2") (pintype "bidirectional"))
      (node (ref "U2") (pin "4") (pinfunction "OUT_4") (pintype "output"))
    )
    (net (code "17") (name "+12V_VMON") (class "Default")
      (node (ref "C39") (pin "1") (pinfunction "1_1") (pintype "passive"))
      (node (ref "R18") (pin "1") (pinfunction "1_1") (pintype "passive"))
      (node (ref "R19") (pin "2") (pinfunction "2_2") (pintype "passive"))
      (node (ref "U$60") (pin "10") (pinfunction "PA05_10") (pintype "bidirectional"))
    )
    (net (code "18") (name "+V_BAT") (class "Default")
      (node (ref "C10") (pin "1") (pinfunction "1_1") (pintype "passive"))
      (node (ref "C11") (pin "1") (pinfunction "1_1") (pintype "passive"))
      (node (ref "C12") (pin "1") (pinfunction "1_1") (pintype "passive"))
      (node (ref "C19") (pin "1") (pinfunction "1_1") (pintype "passive"))
      (node (ref "C20") (pin "1") (pinfunction "1_1") (pintype "passive"))
      (node (ref "C21") (pin "1") (pinfunction "1_1") (pintype "passive"))
      (node (ref "C22") (pin "1") (pinfunction "1_1") (pintype "passive"))
      (node (ref "C23") (pin "1") (pinfunction "1_1") (pintype "passive"))
      (node (ref "C24") (pin "1") (pinfunction "1_1") (pintype "passive"))
      (node (ref "C7") (pin "1") (pinfunction "1_1") (pintype "passive"))
      (node (ref "C8") (pin "1") (pinfunction "1_1") (pintype "passive"))
      (node (ref "C9") (pin "1") (pinfunction "1_1") (pintype "passive"))
      (node (ref "IC1") (pin "6") (pinfunction "OUT_6") (pintype "bidirectional"))
      (node (ref "J3") (pin "1") (pinfunction "1_1") (pintype "passive"))
      (node (ref "J3") (pin "11") (pinfunction "11_11") (pintype "passive"))
      (node (ref "J3") (pin "13") (pinfunction "13_13") (pintype "passive"))
      (node (ref "J3") (pin "15") (pinfunction "15_15") (pintype "passive"))
      (node (ref "J3") (pin "3") (pinfunction "3_3") (pintype "passive"))
      (node (ref "J3") (pin "5") (pinfunction "5_5") (pintype "passive"))
      (node (ref "J3") (pin "7") (pinfunction "7_7") (pintype "passive"))
      (node (ref "J3") (pin "9") (pinfunction "9_9") (pintype "passive"))
      (node (ref "J4") (pin "1") (pinfunction "1_1") (pintype "passive"))
      (node (ref "J4") (pin "11") (pinfunction "11_11") (pintype "passive"))
      (node (ref "J4") (pin "13") (pinfunction "13_13") (pintype "passive"))
      (node (ref "J4") (pin "15") (pinfunction "15_15") (pintype "passive"))
      (node (ref "J4") (pin "3") (pinfunction "3_3") (pintype "passive"))
      (node (ref "J4") (pin "5") (pinfunction "5_5") (pintype "passive"))
      (node (ref "J4") (pin "7") (pinfunction "7_7") (pintype "passive"))
      (node (ref "J4") (pin "9") (pinfunction "9_9") (pintype "passive"))
      (node (ref "Q1") (pin "3") (pinfunction "D_3") (pintype "bidirectional"))
      (node (ref "R22") (pin "2") (pinfunction "2_2") (pintype "passive"))
      (node (ref "R34") (pin "2") (pinfunction "2_2") (pintype "passive"))
      (node (ref "U2") (pin "10") (pinfunction "EN_10") (pintype "passive"))
      (node (ref "U2") (pin "11") (pinfunction "SUP_11") (pintype "passive"))
      (node (ref "U2") (pin "12") (pinfunction "SUPSW_12") (pintype "passive"))
      (node (ref "U3") (pin "10") (pinfunction "EN_10") (pintype "passive"))
      (node (ref "U3") (pin "11") (pinfunction "SUP_11") (pintype "passive"))
      (node (ref "U3") (pin "12") (pinfunction "SUPSW_12") (pintype "passive"))
    )
    (net (code "19") (name "+V_BAT_IMON") (class "Default")
      (node (ref "C50") (pin "1") (pinfunction "1_1") (pintype "passive"))
      (node (ref "R9") (pin "2") (pinfunction "2_2") (pintype "passive"))
      (node (ref "U$60") (pin "13") (pinfunction "PA08_13") (pintype "bidirectional"))
    )
    (net (code "20") (name "+V_BAT_IMON_SENSE_N") (class "Default")
      (node (ref "SH6") (pin "1") (pinfunction "P$1_1") (pintype "bidirectional"))
      (node (ref "U4") (pin "5") (pinfunction "IN-_5") (pintype "bidirectional"))
    )
    (net (code "21") (name "+V_BAT_IMON_SENSE_P1") (class "Default")
      (node (ref "SH5") (pin "1") (pinfunction "P$1_1") (pintype "bidirectional"))
      (node (ref "U4") (pin "4") (pinfunction "IN+_4") (pintype "bidirectional"))
    )
    (net (code "22") (name "+V_BAT_INT") (class "Default")
      (node (ref "F1") (pin "2") (pinfunction "2_2") (pintype "passive"))
      (node (ref "R20") (pin "2") (pinfunction "2_2") (pintype "passive"))
      (node (ref "R5") (pin "1") (pinfunction "1_1") (pintype "passive"))
      (node (ref "SH5") (pin "2") (pinfunction "P$2_2") (pintype "bidirectional"))
    )
    (net (code "23") (name "+V_BAT_INT_VMON") (class "Default")
      (node (ref "C40") (pin "1") (pinfunction "1_1") (pintype "passive"))
      (node (ref "R20") (pin "1") (pinfunction "1_1") (pintype "passive"))
      (node (ref "R21") (pin "2") (pinfunction "2_2") (pintype "passive"))
      (node (ref "U$60") (pin "3") (pinfunction "PA02_3") (pintype "bidirectional"))
    )
    (net (code "24") (name "+V_BAT_VMON") (class "Default")
      (node (ref "C41") (pin "1") (pinfunction "1_1") (pintype "passive"))
      (node (ref "R22") (pin "1") (pinfunction "1_1") (pintype "passive"))
      (node (ref "R23") (pin "2") (pinfunction "2_2") (pintype "passive"))
      (node (ref "U$60") (pin "7") (pinfunction "PB08_7") (pintype "bidirectional"))
    )
    (net (code "25") (name "AGND") (class "Default")
      (node (ref "C28") (pin "2") (pinfunction "2_2") (pintype "passive"))
      (node (ref "U5") (pin "4") (pinfunction "GND_4") (pintype "bidirectional"))
    )
    (net (code "26") (name "CAN0_N") (class "Default")
      (node (ref "J2") (pin "6") (pinfunction "6_6") (pintype "passive"))
      (node (ref "R26") (pin "1") (pinfunction "1_1") (pintype "passive"))
      (node (ref "U7") (pin "6") (pinfunction "CANL_6") (pintype "bidirectional"))
    )
    (net (code "27") (name "CAN0_P") (class "Default")
      (node (ref "J1") (pin "4") (pinfunction "4_4") (pintype "passive"))
      (node (ref "J2") (pin "4") (pinfunction "4_4") (pintype "passive"))
      (node (ref "R26") (pin "2") (pinfunction "2_2") (pintype "passive"))
      (node (ref "U7") (pin "7") (pinfunction "CANH_7") (pintype "bidirectional"))
    )
    (net (code "28") (name "CAN1_N") (class "Default")
      (node (ref "J1") (pin "5") (pinfunction "5_5") (pintype "passive"))
      (node (ref "J2") (pin "5") (pinfunction "5_5") (pintype "passive"))
    )
    (net (code "29") (name "CAN1_P") (class "Default")
      (node (ref "J1") (pin "3") (pinfunction "3_3") (pintype "passive"))
      (node (ref "J2") (pin "3") (pinfunction "3_3") (pintype "passive"))
    )
    (net (code "30") (name "CANRX") (class "Default")
      (node (ref "U$60") (pin "34") (pinfunction "PA25_34") (pintype "bidirectional"))
      (node (ref "U7") (pin "4") (pinfunction "RXD_4") (pintype "bidirectional"))
    )
    (net (code "31") (name "CANTX") (class "Default")
      (node (ref "U$60") (pin "33") (pinfunction "PA24_33") (pintype "bidirectional"))
      (node (ref "U7") (pin "1") (pinfunction "TXD_1") (pintype "bidirectional"))
    )
    (net (code "32") (name "CAN_N") (class "Default")
      (node (ref "J1") (pin "6") (pinfunction "6_6") (pintype "passive"))
    )
    (net (code "33") (name "CAN_STBY") (class "Default")
      (node (ref "U$60") (pin "39") (pinfunction "PA27_39") (pintype "bidirectional"))
      (node (ref "U7") (pin "8") (pinfunction "STBY_8") (pintype "bidirectional"))
    )
    (net (code "34") (name "DETECT_A") (class "Default")
      (node (ref "J1") (pin "10") (pinfunction "10_10") (pintype "passive"))
      (node (ref "U$60") (pin "22") (pinfunction "PA13_22") (pintype "bidirectional"))
    )
    (net (code "35") (name "DETECT_B") (class "Default")
      (node (ref "J2") (pin "10") (pinfunction "10_10") (pintype "passive"))
      (node (ref "U$60") (pin "23") (pinfunction "PA14_23") (pintype "bidirectional"))
    )
    (net (code "36") (name "DGND") (class "Default")
      (node (ref "C13") (pin "2") (pinfunction "2_2") (pintype "passive"))
      (node (ref "C14") (pin "2") (pinfunction "2_2") (pintype "passive"))
      (node (ref "C15") (pin "2") (pinfunction "2_2") (pintype "passive"))
      (node (ref "C2") (pin "2") (pinfunction "2_2") (pintype "passive"))
      (node (ref "C25") (pin "2") (pinfunction "2_2") (pintype "passive"))
      (node (ref "C26") (pin "2") (pinfunction "2_2") (pintype "passive"))
      (node (ref "C27") (pin "2") (pinfunction "2_2") (pintype "passive"))
      (node (ref "C29") (pin "2") (pinfunction "2_2") (pintype "passive"))
      (node (ref "C30") (pin "2") (pinfunction "2_2") (pintype "passive"))
      (node (ref "C31") (pin "2") (pinfunction "2_2") (pintype "passive"))
      (node (ref "C32") (pin "2") (pinfunction "2_2") (pintype "passive"))
      (node (ref "C36") (pin "2") (pinfunction "2_2") (pintype "passive"))
      (node (ref "C37") (pin "2") (pinfunction "2_2") (pintype "passive"))
      (node (ref "C38") (pin "2") (pinfunction "2_2") (pintype "passive"))
      (node (ref "C39") (pin "2") (pinfunction "2_2") (pintype "passive"))
      (node (ref "C40") (pin "2") (pinfunction "2_2") (pintype "passive"))
      (node (ref "C41") (pin "2") (pinfunction "2_2") (pintype "passive"))
      (node (ref "C44") (pin "2") (pinfunction "2_2") (pintype "passive"))
      (node (ref "C46") (pin "2") (pinfunction "2_2") (pintype "passive"))
      (node (ref "C47") (pin "2") (pinfunction "2_2") (pintype "passive"))
      (node (ref "C48") (pin "2") (pinfunction "2_2") (pintype "passive"))
      (node (ref "C49") (pin "2") (pinfunction "2_2") (pintype "passive"))
      (node (ref "C50") (pin "2") (pinfunction "2_2") (pintype "passive"))
      (node (ref "C51") (pin "2") (pinfunction "2_2") (pintype "passive"))
      (node (ref "C52") (pin "2") (pinfunction "2_2") (pintype "passive"))
      (node (ref "J6") (pin "3") (pinfunction "3_GND_3") (pintype "passive"))
      (node (ref "J6") (pin "5") (pinfunction "5_GND_5") (pintype "passive"))
      (node (ref "J6") (pin "9") (pinfunction "9_GND_9") (pintype "passive"))
      (node (ref "R13") (pin "1") (pinfunction "1_1") (pintype "passive"))
      (node (ref "R15") (pin "1") (pinfunction "1_1") (pintype "passive"))
      (node (ref "R17") (pin "1") (pinfunction "1_1") (pintype "passive"))
      (node (ref "R19") (pin "1") (pinfunction "1_1") (pintype "passive"))
      (node (ref "R2") (pin "1") (pinfunction "1_1") (pintype "passive"))
      (node (ref "R21") (pin "1") (pinfunction "1_1") (pintype "passive"))
      (node (ref "R23") (pin "1") (pinfunction "1_1") (pintype "passive"))
      (node (ref "R25") (pin "1") (pinfunction "1_1") (pintype "passive"))
      (node (ref "R30") (pin "2") (pinfunction "2_2") (pintype "passive"))
      (node (ref "R33") (pin "1") (pinfunction "1_1") (pintype "passive"))
      (node (ref "R4") (pin "1") (pinfunction "1_1") (pintype "passive"))
      (node (ref "R8") (pin "2") (pinfunction "2_2") (pintype "passive"))
      (node (ref "U$60") (pin "18") (pinfunction "GND_1_18") (pintype "power_in"))
      (node (ref "U$60") (pin "35") (pinfunction "GND_2_35") (pintype "power_in"))
      (node (ref "U$60") (pin "42") (pinfunction "GND_3_42") (pintype "bidirectional"))
      (node (ref "U$60") (pin "5") (pinfunction "GNDANA_5") (pintype "bidirectional"))
      (node (ref "U2") (pin "8") (pinfunction "AGND_8") (pintype "passive"))
      (node (ref "U3") (pin "8") (pinfunction "AGND_8") (pintype "passive"))
      (node (ref "U4") (pin "1") (pinfunction "REF_1") (pintype "bidirectional"))
      (node (ref "U4") (pin "2") (pinfunction "GND_2") (pintype "bidirectional"))
      (node (ref "U7") (pin "2") (pinfunction "GND_2") (pintype "bidirectional"))
    )
    (net (code "37") (name "ETH_RX+") (class "Default")
      (node (ref "J1") (pin "36") (pinfunction "36_36") (pintype "passive"))
      (node (ref "J2") (pin "36") (pinfunction "36_36") (pintype "passive"))
    )
    (net (code "38") (name "ETH_RX-") (class "Default")
      (node (ref "J1") (pin "38") (pinfunction "38_38") (pintype "passive"))
      (node (ref "J2") (pin "38") (pinfunction "38_38") (pintype "passive"))
    )
    (net (code "39") (name "ETH_TX+") (class "Default")
      (node (ref "J1") (pin "32") (pinfunction "32_32") (pintype "passive"))
      (node (ref "J2") (pin "32") (pinfunction "32_32") (pintype "passive"))
    )
    (net (code "40") (name "ETH_TX-") (class "Default")
      (node (ref "J1") (pin "34") (pinfunction "34_34") (pintype "passive"))
      (node (ref "J2") (pin "34") (pinfunction "34_34") (pintype "passive"))
    )
    (net (code "41") (name "I2C_SCL") (class "Default")
      (node (ref "J1") (pin "22") (pinfunction "22_22") (pintype "passive"))
      (node (ref "J2") (pin "22") (pinfunction "22_22") (pintype "passive"))
    )
    (net (code "42") (name "I2C_SDA") (class "Default")
      (node (ref "J1") (pin "20") (pinfunction "20_20") (pintype "passive"))
      (node (ref "J2") (pin "20") (pinfunction "20_20") (pintype "passive"))
    )
    (net (code "43") (name "Net-(C14-Pad1)") (class "Default")
      (node (ref "C14") (pin "1") (pinfunction "1_1") (pintype "passive"))
      (node (ref "R1") (pin "1") (pinfunction "1_1") (pintype "passive"))
    )
    (net (code "44") (name "Net-(C26-Pad1)") (class "Default")
      (node (ref "C26") (pin "1") (pinfunction "1_1") (pintype "passive"))
      (node (ref "R3") (pin "1") (pinfunction "1_1") (pintype "passive"))
    )
    (net (code "45") (name "Net-(D1-K)") (class "Default")
      (node (ref "C3") (pin "2") (pinfunction "2_2") (pintype "passive"))
      (node (ref "D1") (pin "1") (pinfunction "K_1") (pintype "bidirectional"))
      (node (ref "L1") (pin "1") (pinfunction "1_1") (pintype "bidirectional"))
      (node (ref "U2") (pin "13") (pinfunction "LX_13") (pintype "passive"))
      (node (ref "U2") (pin "14") (pinfunction "LX_2_14") (pintype "passive"))
    )
    (net (code "46") (name "Net-(D2-K)") (class "Default")
      (node (ref "C45") (pin "2") (pinfunction "2_2") (pintype "passive"))
      (node (ref "D2") (pin "1") (pinfunction "K_1") (pintype "bidirectional"))
      (node (ref "L2") (pin "1") (pinfunction "1_1") (pintype "bidirectional"))
      (node (ref "U3") (pin "13") (pinfunction "LX_13") (pintype "passive"))
      (node (ref "U3") (pin "14") (pinfunction "LX_2_14") (pintype "passive"))
    )
    (net (code "47") (name "Net-(IC1-GATE)") (class "Default")
      (node (ref "IC1") (pin "5") (pinfunction "GATE_5") (pintype "bidirectional"))
      (node (ref "Q1") (pin "1") (pinfunction "G_1") (pintype "bidirectional"))
    )
    (net (code "48") (name "Net-(IC1-IN)") (class "Default")
      (node (ref "IC1") (pin "4") (pinfunction "IN_4") (pintype "bidirectional"))
      (node (ref "Q1") (pin "2") (pinfunction "S_2") (pintype "bidirectional"))
      (node (ref "R5") (pin "2") (pinfunction "2_2") (pintype "passive"))
      (node (ref "SH6") (pin "2") (pinfunction "P$2_2") (pintype "bidirectional"))
    )
    (net (code "49") (name "Net-(IC1-VS)") (class "Default")
      (node (ref "C33") (pin "1") (pinfunction "1_1") (pintype "passive"))
      (node (ref "IC1") (pin "1") (pinfunction "VS_1") (pintype "bidirectional"))
      (node (ref "R34") (pin "1") (pinfunction "1_1") (pintype "passive"))
    )
    (net (code "50") (name "Net-(IC2-GATE)") (class "Default")
      (node (ref "IC2") (pin "5") (pinfunction "GATE_5") (pintype "bidirectional"))
      (node (ref "Q2") (pin "1") (pinfunction "G_1") (pintype "bidirectional"))
    )
    (net (code "51") (name "Net-(IC2-IN)") (class "Default")
      (node (ref "IC2") (pin "4") (pinfunction "IN_4") (pintype "bidirectional"))
      (node (ref "Q2") (pin "2") (pinfunction "S_2") (pintype "bidirectional"))
      (node (ref "R6") (pin "2") (pinfunction "2_2") (pintype "passive"))
      (node (ref "SH4") (pin "2") (pinfunction "P$2_2") (pintype "bidirectional"))
    )
    (net (code "52") (name "Net-(IC2-VS)") (class "Default")
      (node (ref "C34") (pin "1") (pinfunction "1_1") (pintype "passive"))
      (node (ref "IC2") (pin "1") (pinfunction "VS_1") (pintype "bidirectional"))
      (node (ref "R27") (pin "1") (pinfunction "1_1") (pintype "passive"))
    )
    (net (code "53") (name "Net-(IC3-GATE)") (class "Default")
      (node (ref "IC3") (pin "5") (pinfunction "GATE_5") (pintype "bidirectional"))
      (node (ref "Q3") (pin "1") (pinfunction "G_1") (pintype "bidirectional"))
    )
    (net (code "54") (name "Net-(IC3-IN)") (class "Default")
      (node (ref "IC3") (pin "4") (pinfunction "IN_4") (pintype "bidirectional"))
      (node (ref "Q3") (pin "2") (pinfunction "S_2") (pintype "bidirectional"))
      (node (ref "R7") (pin "2") (pinfunction "2_2") (pintype "passive"))
      (node (ref "SH2") (pin "2") (pinfunction "P$2_2") (pintype "bidirectional"))
    )
    (net (code "55") (name "Net-(IC3-VS)") (class "Default")
      (node (ref "C35") (pin "1") (pinfunction "1_1") (pintype "passive"))
      (node (ref "IC3") (pin "1") (pinfunction "VS_1") (pintype "bidirectional"))
      (node (ref "R28") (pin "1") (pinfunction "1_1") (pintype "passive"))
    )
    (net (code "56") (name "Net-(U$13-TP)") (class "Default")
      (node (ref "F1") (pin "1") (pinfunction "1_1") (pintype "passive"))
      (node (ref "U$13") (pin "P$1") (pinfunction "TP_P$1") (pintype "input"))
    )
    (net (code "57") (name "Net-(U$60A-VDDCORE)") (class "Default")
      (node (ref "C46") (pin "1") (pinfunction "1_1") (pintype "passive"))
      (node (ref "C47") (pin "1") (pinfunction "1_1") (pintype "passive"))
      (node (ref "U$60") (pin "43") (pinfunction "VDDCORE_43") (pintype "power_in"))
    )
    (net (code "58") (name "Net-(U$60B-PA12)") (class "Default")
      (node (ref "D4") (pin "A") (pinfunction "A_A") (pintype "passive"))
      (node (ref "U$60") (pin "21") (pinfunction "PA12_21") (pintype "bidirectional"))
    )
    (net (code "59") (name "Net-(U2-BIAS)") (class "Default")
      (node (ref "C15") (pin "1") (pinfunction "1_1") (pintype "passive"))
      (node (ref "U2") (pin "2") (pinfunction "FSYNC_2") (pintype "passive"))
      (node (ref "U2") (pin "7") (pinfunction "BIAS_7") (pintype "passive"))
    )
    (net (code "60") (name "Net-(U2-BST)") (class "Default")
      (node (ref "C3") (pin "1") (pinfunction "1_1") (pintype "passive"))
      (node (ref "U2") (pin "9") (pinfunction "BST_9") (pintype "passive"))
    )
    (net (code "61") (name "Net-(U2-COMP)") (class "Default")
      (node (ref "C13") (pin "1") (pinfunction "1_1") (pintype "passive"))
      (node (ref "R1") (pin "2") (pinfunction "2_2") (pintype "passive"))
      (node (ref "U2") (pin "6") (pinfunction "COMP_6") (pintype "passive"))
    )
    (net (code "62") (name "Net-(U2-FOSC)") (class "Default")
      (node (ref "R2") (pin "2") (pinfunction "2_2") (pintype "passive"))
      (node (ref "U2") (pin "3") (pinfunction "FOSC_3") (pintype "passive"))
    )
    (net (code "63") (name "Net-(U3-BST)") (class "Default")
      (node (ref "C45") (pin "1") (pinfunction "1_1") (pintype "passive"))
      (node (ref "U3") (pin "9") (pinfunction "BST_9") (pintype "passive"))
    )
    (net (code "64") (name "Net-(U3-COMP)") (class "Default")
      (node (ref "C25") (pin "1") (pinfunction "1_1") (pintype "passive"))
      (node (ref "R3") (pin "2") (pinfunction "2_2") (pintype "passive"))
      (node (ref "U3") (pin "6") (pinfunction "COMP_6") (pintype "passive"))
    )
    (net (code "65") (name "Net-(U3-FOSC)") (class "Default")
      (node (ref "R4") (pin "2") (pinfunction "2_2") (pintype "passive"))
      (node (ref "U3") (pin "3") (pinfunction "FOSC_3") (pintype "passive"))
    )
    (net (code "66") (name "Net-(U4-OUT)") (class "Default")
      (node (ref "R9") (pin "1") (pinfunction "1_1") (pintype "passive"))
      (node (ref "U4") (pin "6") (pinfunction "OUT_6") (pintype "bidirectional"))
    )
    (net (code "67") (name "Net-(U5A-OUT_1)") (class "Default")
      (node (ref "R10") (pin "1") (pinfunction "1_1") (pintype "passive"))
      (node (ref "U5") (pin "1") (pinfunction "OUT_1_1") (pintype "bidirectional"))
    )
    (net (code "68") (name "Net-(U5B-OUT2)") (class "Default")
      (node (ref "R11") (pin "1") (pinfunction "1_1") (pintype "passive"))
      (node (ref "U5") (pin "7") (pinfunction "OUT2_7") (pintype "bidirectional"))
    )
    (net (code "69") (name "PGND") (class "Default")
      (node (ref "C1") (pin "2") (pinfunction "2_2") (pintype "passive"))
      (node (ref "C10") (pin "2") (pinfunction "2_2") (pintype "passive"))
      (node (ref "C11") (pin "2") (pinfunction "2_2") (pintype "passive"))
      (node (ref "C12") (pin "2") (pinfunction "2_2") (pintype "passive"))
      (node (ref "C16") (pin "2") (pinfunction "2_2") (pintype "passive"))
      (node (ref "C17") (pin "2") (pinfunction "2_2") (pintype "passive"))
      (node (ref "C18") (pin "2") (pinfunction "2_2") (pintype "passive"))
      (node (ref "C19") (pin "2") (pinfunction "2_2") (pintype "passive"))
      (node (ref "C20") (pin "2") (pinfunction "2_2") (pintype "passive"))
      (node (ref "C21") (pin "2") (pinfunction "2_2") (pintype "passive"))
      (node (ref "C22") (pin "2") (pinfunction "2_2") (pintype "passive"))
      (node (ref "C23") (pin "2") (pinfunction "2_2") (pintype "passive"))
      (node (ref "C24") (pin "2") (pinfunction "2_2") (pintype "passive"))
      (node (ref "C33") (pin "2") (pinfunction "2_2") (pintype "passive"))
      (node (ref "C34") (pin "2") (pinfunction "2_2") (pintype "passive"))
      (node (ref "C35") (pin "2") (pinfunction "2_2") (pintype "passive"))
      (node (ref "C4") (pin "2") (pinfunction "2_2") (pintype "passive"))
      (node (ref "C5") (pin "2") (pinfunction "2_2") (pintype "passive"))
      (node (ref "C6") (pin "2") (pinfunction "2_2") (pintype "passive"))
      (node (ref "C7") (pin "2") (pinfunction "2_2") (pintype "passive"))
      (node (ref "C8") (pin "2") (pinfunction "2_2") (pintype "passive"))
      (node (ref "C9") (pin "2") (pinfunction "2_2") (pintype "passive"))
      (node (ref "D1") (pin "2") (pinfunction "A_2") (pintype "bidirectional"))
      (node (ref "D2") (pin "2") (pinfunction "A_2") (pintype "bidirectional"))
      (node (ref "IC1") (pin "2") (pinfunction "GND_2") (pintype "bidirectional"))
      (node (ref "IC1") (pin "3") (pinfunction "OFF_3") (pintype "bidirectional"))
      (node (ref "IC2") (pin "2") (pinfunction "GND_2") (pintype "bidirectional"))
      (node (ref "IC2") (pin "3") (pinfunction "OFF_3") (pintype "bidirectional"))
      (node (ref "IC3") (pin "2") (pinfunction "GND_2") (pintype "bidirectional"))
      (node (ref "IC3") (pin "3") (pinfunction "OFF_3") (pintype "bidirectional"))
      (node (ref "J3") (pin "10") (pinfunction "10_10") (pintype "passive"))
      (node (ref "J3") (pin "12") (pinfunction "12_12") (pintype "passive"))
      (node (ref "J3") (pin "14") (pinfunction "14_14") (pintype "passive"))
      (node (ref "J3") (pin "16") (pinfunction "16_16") (pintype "passive"))
      (node (ref "J3") (pin "18") (pinfunction "18_18") (pintype "passive"))
      (node (ref "J3") (pin "2") (pinfunction "2_2") (pintype "passive"))
      (node (ref "J3") (pin "20") (pinfunction "20_20") (pintype "passive"))
      (node (ref "J3") (pin "22") (pinfunction "22_22") (pintype "passive"))
      (node (ref "J3") (pin "24") (pinfunction "24_24") (pintype "passive"))
      (node (ref "J3") (pin "26") (pinfunction "26_26") (pintype "passive"))
      (node (ref "J3") (pin "28") (pinfunction "28_28") (pintype "passive"))
      (node (ref "J3") (pin "30") (pinfunction "30_30") (pintype "passive"))
      (node (ref "J3") (pin "32") (pinfunction "32_32") (pintype "passive"))
      (node (ref "J3") (pin "34") (pinfunction "34_34") (pintype "passive"))
      (node (ref "J3") (pin "36") (pinfunction "36_36") (pintype "passive"))
      (node (ref "J3") (pin "38") (pinfunction "38_38") (pintype "passive"))
      (node (ref "J3") (pin "4") (pinfunction "4_4") (pintype "passive"))
      (node (ref "J3") (pin "40") (pinfunction "40_40") (pintype "passive"))
      (node (ref "J3") (pin "6") (pinfunction "6_6") (pintype "passive"))
      (node (ref "J3") (pin "8") (pinfunction "8_8") (pintype "passive"))
      (node (ref "J4") (pin "10") (pinfunction "10_10") (pintype "passive"))
      (node (ref "J4") (pin "12") (pinfunction "12_12") (pintype "passive"))
      (node (ref "J4") (pin "14") (pinfunction "14_14") (pintype "passive"))
      (node (ref "J4") (pin "16") (pinfunction "16_16") (pintype "passive"))
      (node (ref "J4") (pin "18") (pinfunction "18_18") (pintype "passive"))
      (node (ref "J4") (pin "2") (pinfunction "2_2") (pintype "passive"))
      (node (ref "J4") (pin "20") (pinfunction "20_20") (pintype "passive"))
      (node (ref "J4") (pin "22") (pinfunction "22_22") (pintype "passive"))
      (node (ref "J4") (pin "24") (pinfunction "24_24") (pintype "passive"))
      (node (ref "J4") (pin "26") (pinfunction "26_26") (pintype "passive"))
      (node (ref "J4") (pin "28") (pinfunction "28_28") (pintype "passive"))
      (node (ref "J4") (pin "30") (pinfunction "30_30") (pintype "passive"))
      (node (ref "J4") (pin "32") (pinfunction "32_32") (pintype "passive"))
      (node (ref "J4") (pin "34") (pinfunction "34_34") (pintype "passive"))
      (node (ref "J4") (pin "36") (pinfunction "36_36") (pintype "passive"))
      (node (ref "J4") (pin "38") (pinfunction "38_38") (pintype "passive"))
      (node (ref "J4") (pin "4") (pinfunction "4_4") (pintype "passive"))
      (node (ref "J4") (pin "40") (pinfunction "40_40") (pintype "passive"))
      (node (ref "J4") (pin "6") (pinfunction "6_6") (pintype "passive"))
      (node (ref "J4") (pin "8") (pinfunction "8_8") (pintype "passive"))
      (node (ref "R30") (pin "1") (pinfunction "1_1") (pintype "passive"))
      (node (ref "R32") (pin "1") (pinfunction "1_1") (pintype "passive"))
      (node (ref "U$9") (pin "P$1") (pinfunction "TP_P$1") (pintype "input"))
      (node (ref "U2") (pin "15") (pinfunction "PGND_15") (pintype "passive"))
      (node (ref "U2") (pin "17") (pinfunction "EPAD_17") (pintype "passive"))
      (node (ref "U3") (pin "15") (pinfunction "PGND_15") (pintype "passive"))
      (node (ref "U3") (pin "17") (pinfunction "EPAD_17") (pintype "passive"))
      (node (ref "U6") (pin "2") (pinfunction "GND_1_2") (pintype "bidirectional"))
      (node (ref "U6") (pin "5") (pinfunction "GND_2_5") (pintype "bidirectional"))
    )
    (net (code "70") (name "PGOOD_+3.5V") (class "Default")
      (node (ref "U$60") (pin "19") (pinfunction "PB10_19") (pintype "bidirectional"))
      (node (ref "U3") (pin "16") (pinfunction "~{PGOOD}_16") (pintype "passive"))
    )
    (net (code "71") (name "PGOOD_+5V") (class "Default")
      (node (ref "U$60") (pin "20") (pinfunction "PB11_20") (pintype "bidirectional"))
      (node (ref "U2") (pin "16") (pinfunction "~{PGOOD}_16") (pintype "passive"))
    )
    (net (code "72") (name "P_GOOD") (class "Default")
      (node (ref "D4") (pin "C") (pinfunction "C_C") (pintype "passive"))
      (node (ref "J3") (pin "39") (pinfunction "39_39") (pintype "passive"))
      (node (ref "J4") (pin "39") (pinfunction "39_39") (pintype "passive"))
      (node (ref "R32") (pin "2") (pinfunction "2_2") (pintype "passive"))
    )
    (net (code "73") (name "RESET") (class "Default")
      (node (ref "J6") (pin "10") (pinfunction "10_RESET_10") (pintype "passive"))
      (node (ref "U$60") (pin "40") (pinfunction "~{RESET}_40") (pintype "input"))
    )
    (net (code "74") (name "RFU_9") (class "Default")
      (node (ref "J1") (pin "9") (pinfunction "9_9") (pintype "passive"))
      (node (ref "J2") (pin "9") (pinfunction "9_9") (pintype "passive"))
    )
    (net (code "75") (name "RFU_11") (class "Default")
      (node (ref "J1") (pin "11") (pinfunction "11_11") (pintype "passive"))
      (node (ref "J2") (pin "11") (pinfunction "11_11") (pintype "passive"))
    )
    (net (code "76") (name "RFU_13") (class "Default")
      (node (ref "J1") (pin "13") (pinfunction "13_13") (pintype "passive"))
      (node (ref "J2") (pin "13") (pinfunction "13_13") (pintype "passive"))
    )
    (net (code "77") (name "RFU_15") (class "Default")
      (node (ref "J1") (pin "15") (pinfunction "15_15") (pintype "passive"))
      (node (ref "J2") (pin "15") (pinfunction "15_15") (pintype "passive"))
    )
    (net (code "78") (name "RFU_17") (class "Default")
      (node (ref "J1") (pin "17") (pinfunction "17_17") (pintype "passive"))
      (node (ref "J2") (pin "17") (pinfunction "17_17") (pintype "passive"))
    )
    (net (code "79") (name "RFU_19") (class "Default")
      (node (ref "J1") (pin "19") (pinfunction "19_19") (pintype "passive"))
      (node (ref "J2") (pin "19") (pinfunction "19_19") (pintype "passive"))
    )
    (net (code "80") (name "RFU_21") (class "Default")
      (node (ref "J1") (pin "21") (pinfunction "21_21") (pintype "passive"))
      (node (ref "J2") (pin "21") (pinfunction "21_21") (pintype "passive"))
    )
    (net (code "81") (name "RFU_23") (class "Default")
      (node (ref "J1") (pin "23") (pinfunction "23_23") (pintype "passive"))
      (node (ref "J2") (pin "23") (pinfunction "23_23") (pintype "passive"))
    )
    (net (code "82") (name "RFU_25") (class "Default")
      (node (ref "J1") (pin "25") (pinfunction "25_25") (pintype "passive"))
      (node (ref "J2") (pin "25") (pinfunction "25_25") (pintype "passive"))
    )
    (net (code "83") (name "RFU_27") (class "Default")
      (node (ref "J1") (pin "27") (pinfunction "27_27") (pintype "passive"))
      (node (ref "J2") (pin "27") (pinfunction "27_27") (pintype "passive"))
    )
    (net (code "84") (name "RFU_29") (class "Default")
      (node (ref "J1") (pin "29") (pinfunction "29_29") (pintype "passive"))
      (node (ref "J2") (pin "29") (pinfunction "29_29") (pintype "passive"))
    )
    (net (code "85") (name "RFU_31") (class "Default")
      (node (ref "J1") (pin "31") (pinfunction "31_31") (pintype "passive"))
      (node (ref "J2") (pin "31") (pinfunction "31_31") (pintype "passive"))
    )
    (net (code "86") (name "RFU_33") (class "Default")
      (node (ref "J1") (pin "33") (pinfunction "33_33") (pintype "passive"))
      (node (ref "J2") (pin "33") (pinfunction "33_33") (pintype "passive"))
    )
    (net (code "87") (name "RFU_35") (class "Default")
      (node (ref "J1") (pin "35") (pinfunction "35_35") (pintype "passive"))
      (node (ref "J2") (pin "35") (pinfunction "35_35") (pintype "passive"))
    )
    (net (code "88") (name "RFU_37") (class "Default")
      (node (ref "J1") (pin "37") (pinfunction "37_37") (pintype "passive"))
      (node (ref "J2") (pin "37") (pinfunction "37_37") (pintype "passive"))
    )
    (net (code "89") (name "RS485_D+") (class "Default")
      (node (ref "J1") (pin "26") (pinfunction "26_26") (pintype "passive"))
      (node (ref "J2") (pin "26") (pinfunction "26_26") (pintype "passive"))
    )
    (net (code "90") (name "RS485_D-") (class "Default")
      (node (ref "J1") (pin "28") (pinfunction "28_28") (pintype "passive"))
      (node (ref "J2") (pin "28") (pinfunction "28_28") (pintype "passive"))
    )
    (net (code "91") (name "SHIELD") (class "Default")
      (node (ref "J1") (pin "1") (pinfunction "1_1") (pintype "passive"))
      (node (ref "J1") (pin "18") (pinfunction "18_18") (pintype "passive"))
      (node (ref "J1") (pin "2") (pinfunction "2_2") (pintype "passive"))
      (node (ref "J1") (pin "24") (pinfunction "24_24") (pintype "passive"))
      (node (ref "J1") (pin "30") (pinfunction "30_30") (pintype "passive"))
      (node (ref "J1") (pin "39") (pinfunction "39_39") (pintype "passive"))
      (node (ref "J1") (pin "40") (pinfunction "40_40") (pintype "passive"))
      (node (ref "J1") (pin "7") (pinfunction "7_7") (pintype "passive"))
      (node (ref "J1") (pin "8") (pinfunction "8_8") (pintype "passive"))
      (node (ref "J2") (pin "1") (pinfunction "1_1") (pintype "passive"))
      (node (ref "J2") (pin "18") (pinfunction "18_18") (pintype "passive"))
      (node (ref "J2") (pin "2") (pinfunction "2_2") (pintype "passive"))
      (node (ref "J2") (pin "24") (pinfunction "24_24") (pintype "passive"))
      (node (ref "J2") (pin "30") (pinfunction "30_30") (pintype "passive"))
      (node (ref "J2") (pin "39") (pinfunction "39_39") (pintype "passive"))
      (node (ref "J2") (pin "40") (pinfunction "40_40") (pintype "passive"))
      (node (ref "J2") (pin "7") (pinfunction "7_7") (pintype "passive"))
      (node (ref "J2") (pin "8") (pinfunction "8_8") (pintype "passive"))
      (node (ref "R8") (pin "1") (pinfunction "1_1") (pintype "passive"))
    )
    (net (code "92") (name "SPI_MISO") (class "Default")
      (node (ref "J1") (pin "12") (pinfunction "12_12") (pintype "passive"))
      (node (ref "J2") (pin "12") (pinfunction "12_12") (pintype "passive"))
    )
    (net (code "93") (name "SPI_MOSI") (class "Default")
      (node (ref "J1") (pin "14") (pinfunction "14_14") (pintype "passive"))
      (node (ref "J2") (pin "14") (pinfunction "14_14") (pintype "passive"))
    )
    (net (code "94") (name "SPI_SCK") (class "Default")
      (node (ref "J1") (pin "16") (pinfunction "16_16") (pintype "passive"))
      (node (ref "J2") (pin "16") (pinfunction "16_16") (pintype "passive"))
    )
    (net (code "95") (name "SWCLK") (class "Default")
      (node (ref "J6") (pin "4") (pinfunction "4_SWCLK_4") (pintype "passive"))
      (node (ref "R35") (pin "1") (pinfunction "1_1") (pintype "passive"))
      (node (ref "U$60") (pin "45") (pinfunction "PA30/SWCLK_45") (pintype "bidirectional"))
    )
    (net (code "96") (name "SWDIO") (class "Default")
      (node (ref "J6") (pin "2") (pinfunction "2SWDIO_2") (pintype "passive"))
      (node (ref "U$60") (pin "46") (pinfunction "PA31/SWDIO_46") (pintype "bidirectional"))
    )
    (net (code "97") (name "VBIAS_U3") (class "Default")
      (node (ref "C27") (pin "1") (pinfunction "1_1") (pintype "passive"))
      (node (ref "U3") (pin "2") (pinfunction "FSYNC_2") (pintype "passive"))
      (node (ref "U3") (pin "5") (pinfunction "FB_5") (pintype "passive"))
      (node (ref "U3") (pin "7") (pinfunction "BIAS_7") (pintype "passive"))
    )
    (net (code "98") (name "unconnected-(J6-6_SWO-Pad6)") (class "Default")
      (node (ref "J6") (pin "6") (pinfunction "6_SWO_6") (pintype "passive"))
    )
    (net (code "99") (name "unconnected-(J6-7_NC-Pad7)") (class "Default")
      (node (ref "J6") (pin "7") (pinfunction "7_NC_7") (pintype "passive"))
    )
    (net (code "100") (name "unconnected-(J6-8_NC-Pad8)") (class "Default")
      (node (ref "J6") (pin "8") (pinfunction "8_NC_8") (pintype "passive"))
    )
    (net (code "101") (name "unconnected-(U$60B-PA00-Pad1)") (class "Default")
      (node (ref "U$60") (pin "1") (pinfunction "PA00_1") (pintype "bidirectional"))
    )
    (net (code "102") (name "unconnected-(U$60B-PA01-Pad2)") (class "Default")
      (node (ref "U$60") (pin "2") (pinfunction "PA01_2") (pintype "bidirectional"))
    )
    (net (code "103") (name "unconnected-(U$60B-PA10-Pad15)") (class "Default")
      (node (ref "U$60") (pin "15") (pinfunction "PA10_15") (pintype "bidirectional"))
    )
    (net (code "104") (name "unconnected-(U$60B-PA11-Pad16)") (class "Default")
      (node (ref "U$60") (pin "16") (pinfunction "PA11_16") (pintype "bidirectional"))
    )
    (net (code "105") (name "unconnected-(U$60B-PA15-Pad24)") (class "Default")
      (node (ref "U$60") (pin "24") (pinfunction "PA15_24") (pintype "bidirectional"))
    )
    (net (code "106") (name "unconnected-(U$60B-PA16-Pad25)") (class "Default")
      (node (ref "U$60") (pin "25") (pinfunction "PA16_25") (pintype "bidirectional"))
    )
    (net (code "107") (name "unconnected-(U$60B-PA17-Pad26)") (class "Default")
      (node (ref "U$60") (pin "26") (pinfunction "PA17_26") (pintype "bidirectional"))
    )
    (net (code "108") (name "unconnected-(U$60B-PA18-Pad27)") (class "Default")
      (node (ref "U$60") (pin "27") (pinfunction "PA18_27") (pintype "bidirectional"))
    )
    (net (code "109") (name "unconnected-(U$60B-PA19-Pad28)") (class "Default")
      (node (ref "U$60") (pin "28") (pinfunction "PA19_28") (pintype "bidirectional"))
    )
    (net (code "110") (name "unconnected-(U$60B-PA20-Pad29)") (class "Default")
      (node (ref "U$60") (pin "29") (pinfunction "PA20_29") (pintype "bidirectional"))
    )
    (net (code "111") (name "unconnected-(U$60B-PA21-Pad30)") (class "Default")
      (node (ref "U$60") (pin "30") (pinfunction "PA21_30") (pintype "bidirectional"))
    )
    (net (code "112") (name "unconnected-(U$60B-PA22-Pad31)") (class "Default")
      (node (ref "U$60") (pin "31") (pinfunction "PA22_31") (pintype "bidirectional"))
    )
    (net (code "113") (name "unconnected-(U$60B-PA23-Pad32)") (class "Default")
      (node (ref "U$60") (pin "32") (pinfunction "PA23_32") (pintype "bidirectional"))
    )
    (net (code "114") (name "unconnected-(U$60B-PA28-Pad41)") (class "Default")
      (node (ref "U$60") (pin "41") (pinfunction "PA28_41") (pintype "bidirectional"))
    )
    (net (code "115") (name "unconnected-(U$60B-PB02-Pad47)") (class "Default")
      (node (ref "U$60") (pin "47") (pinfunction "PB02_47") (pintype "bidirectional"))
    )
    (net (code "116") (name "unconnected-(U$60B-PB03-Pad48)") (class "Default")
      (node (ref "U$60") (pin "48") (pinfunction "PB03_48") (pintype "bidirectional"))
    )
    (net (code "117") (name "unconnected-(U$60B-PB22-Pad37)") (class "Default")
      (node (ref "U$60") (pin "37") (pinfunction "PB22_37") (pintype "bidirectional"))
    )
    (net (code "118") (name "unconnected-(U$60B-PB23-Pad38)") (class "Default")
      (node (ref "U$60") (pin "38") (pinfunction "PB23_38") (pintype "bidirectional"))
    )
    (net (code "119") (name "unconnected-(U2-SYNCOUT-Pad1)") (class "Default")
      (node (ref "U2") (pin "1") (pinfunction "SYNCOUT_1") (pintype "output"))
    )
    (net (code "120") (name "unconnected-(U3-SYNCOUT-Pad1)") (class "Default")
      (node (ref "U3") (pin "1") (pinfunction "SYNCOUT_1") (pintype "output"))
    )
    (net (code "121") (name "unconnected-(U6-NC-Pad4)") (class "Default")
      (node (ref "U6") (pin "4") (pinfunction "NC_4") (pintype "no_connect"))
    )
  )
)
